# 8iPanel.net
KiCad netlist of a schematic drawn in EAGLE
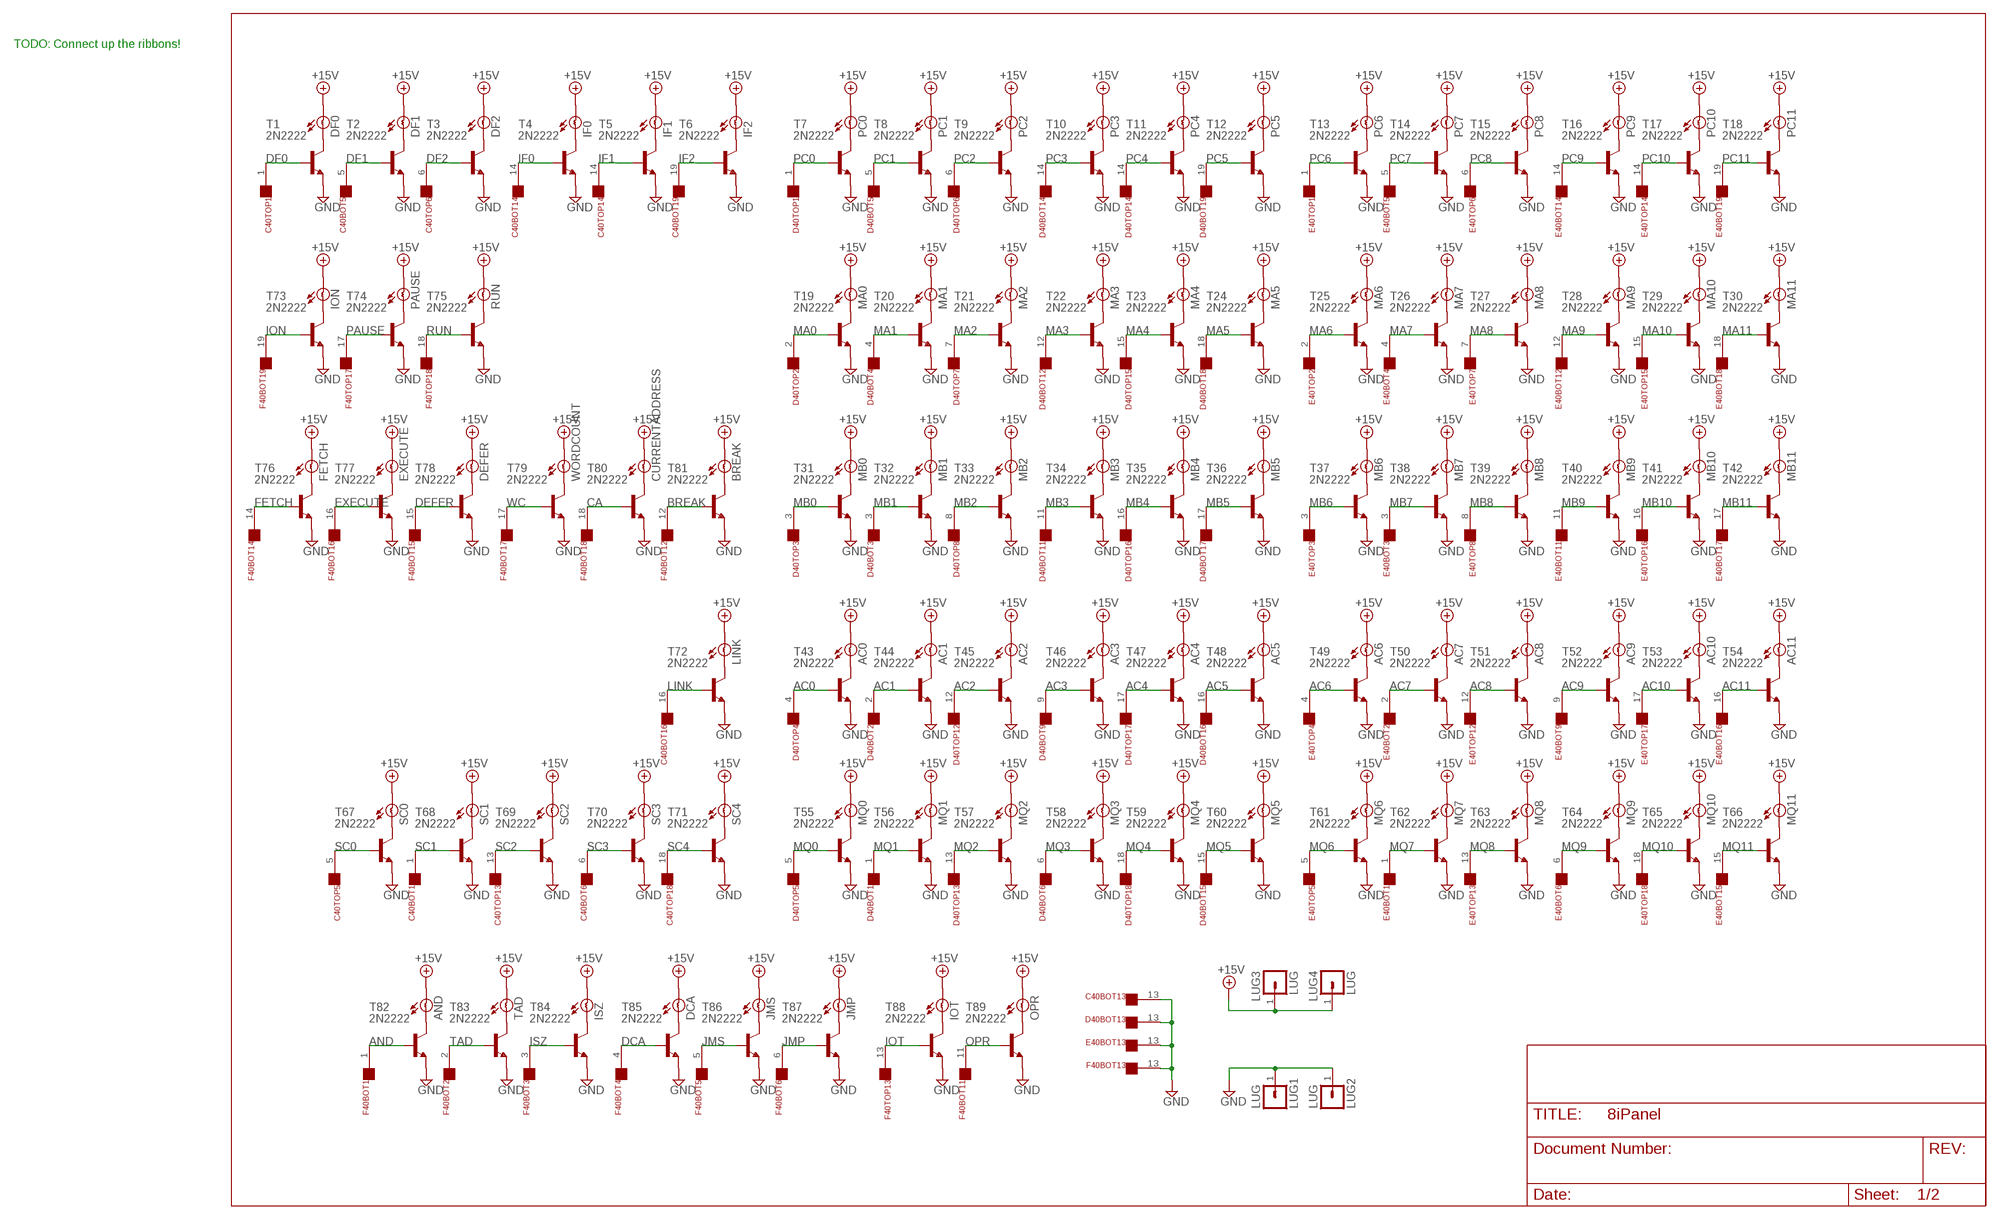
[diagram p0: schematic, sheet 1]
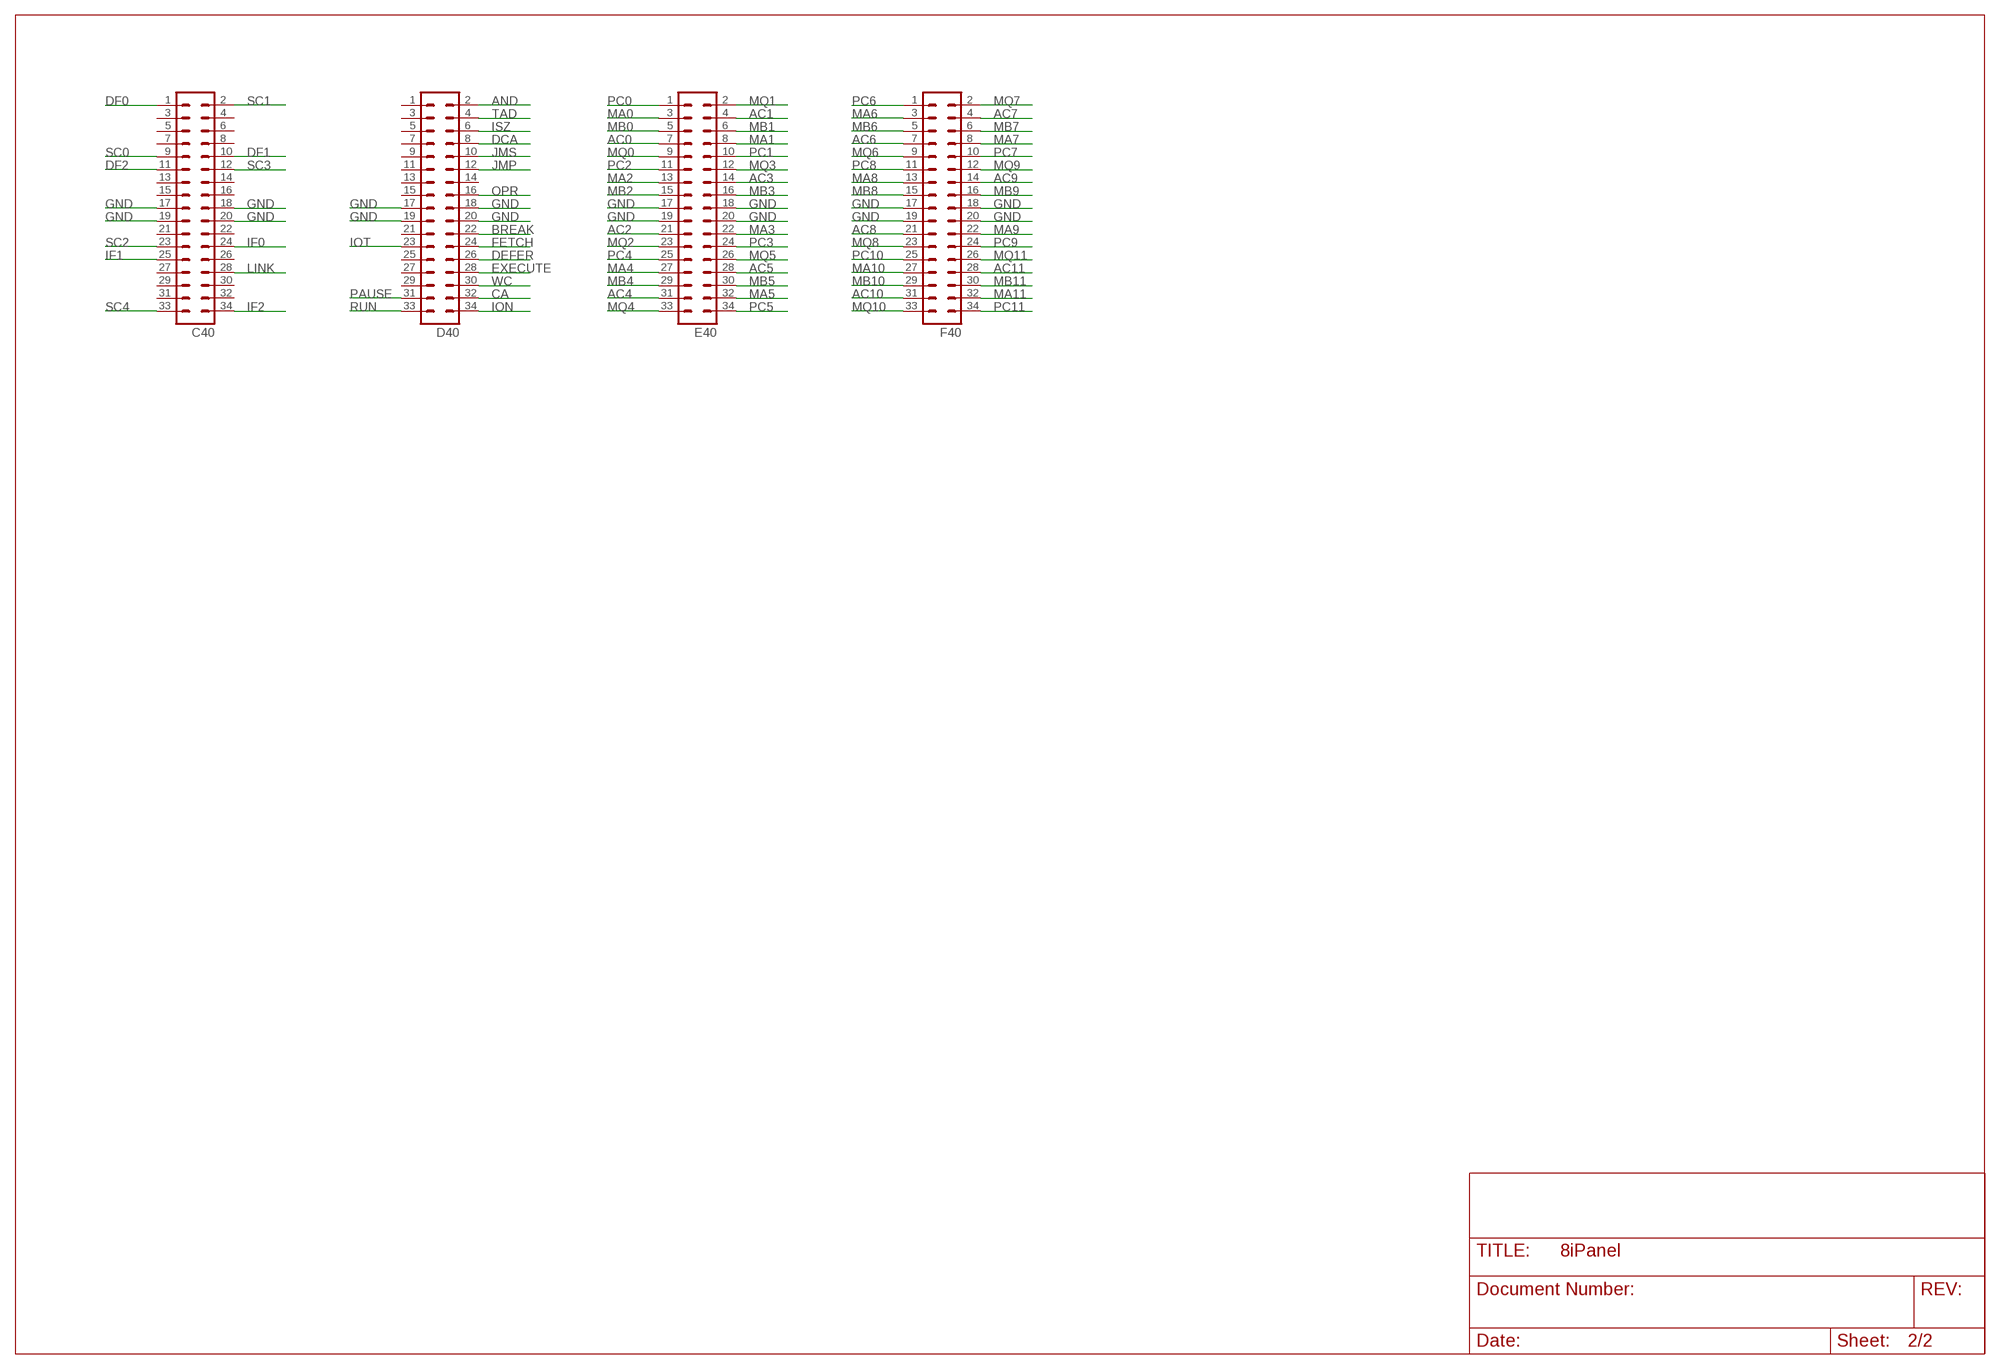
[diagram p1: schematic, sheet 2]

(export (version "E")
  (design (tool "Eeschema 10.0.6"))
  (components
    (comp (ref "AC0")
      (value "BULB")
      (footprint "eagle-import:BULB")
      (libsource (lib "eagle-import") (part "BULB"))
    )
    (comp (ref "AC1")
      (value "BULB")
      (footprint "eagle-import:BULB")
      (libsource (lib "eagle-import") (part "BULB"))
    )
    (comp (ref "AC2")
      (value "BULB")
      (footprint "eagle-import:BULB")
      (libsource (lib "eagle-import") (part "BULB"))
    )
    (comp (ref "AC3")
      (value "BULB")
      (footprint "eagle-import:BULB")
      (libsource (lib "eagle-import") (part "BULB"))
    )
    (comp (ref "AC4")
      (value "BULB")
      (footprint "eagle-import:BULB")
      (libsource (lib "eagle-import") (part "BULB"))
    )
    (comp (ref "AC5")
      (value "BULB")
      (footprint "eagle-import:BULB")
      (libsource (lib "eagle-import") (part "BULB"))
    )
    (comp (ref "AC6")
      (value "BULB")
      (footprint "eagle-import:BULB")
      (libsource (lib "eagle-import") (part "BULB"))
    )
    (comp (ref "AC7")
      (value "BULB")
      (footprint "eagle-import:BULB")
      (libsource (lib "eagle-import") (part "BULB"))
    )
    (comp (ref "AC8")
      (value "BULB")
      (footprint "eagle-import:BULB")
      (libsource (lib "eagle-import") (part "BULB"))
    )
    (comp (ref "AC9")
      (value "BULB")
      (footprint "eagle-import:BULB")
      (libsource (lib "eagle-import") (part "BULB"))
    )
    (comp (ref "AC10")
      (value "BULB")
      (footprint "eagle-import:BULB")
      (libsource (lib "eagle-import") (part "BULB"))
    )
    (comp (ref "AC11")
      (value "BULB")
      (footprint "eagle-import:BULB")
      (libsource (lib "eagle-import") (part "BULB"))
    )
    (comp (ref "AND")
      (value "BULB")
      (footprint "eagle-import:BULB")
      (libsource (lib "eagle-import") (part "BULB"))
    )
    (comp (ref "BREAK")
      (value "BULB")
      (footprint "eagle-import:BULB")
      (libsource (lib "eagle-import") (part "BULB"))
    )
    (comp (ref "C40BOT")
      (value "FLEX19")
      (footprint "eagle-import:FLEX19")
      (libsource (lib "eagle-import") (part "FLEX19"))
    )
    (comp (ref "C40TOP")
      (value "FLEX19")
      (footprint "eagle-import:FLEX19")
      (libsource (lib "eagle-import") (part "FLEX19"))
    )
    (comp (ref "CURRENTADDRESS")
      (value "BULB")
      (footprint "eagle-import:BULB")
      (libsource (lib "eagle-import") (part "BULB"))
    )
    (comp (ref "D40BOT")
      (value "FLEX19")
      (footprint "eagle-import:FLEX19")
      (libsource (lib "eagle-import") (part "FLEX19"))
    )
    (comp (ref "D40TOP")
      (value "FLEX19")
      (footprint "eagle-import:FLEX19")
      (libsource (lib "eagle-import") (part "FLEX19"))
    )
    (comp (ref "DCA")
      (value "BULB")
      (footprint "eagle-import:BULB")
      (libsource (lib "eagle-import") (part "BULB"))
    )
    (comp (ref "DEFER")
      (value "BULB")
      (footprint "eagle-import:BULB")
      (libsource (lib "eagle-import") (part "BULB"))
    )
    (comp (ref "DF0")
      (value "BULB")
      (footprint "eagle-import:BULB")
      (libsource (lib "eagle-import") (part "BULB"))
    )
    (comp (ref "DF1")
      (value "BULB")
      (footprint "eagle-import:BULB")
      (libsource (lib "eagle-import") (part "BULB"))
    )
    (comp (ref "DF2")
      (value "BULB")
      (footprint "eagle-import:BULB")
      (libsource (lib "eagle-import") (part "BULB"))
    )
    (comp (ref "E40BOT")
      (value "FLEX19")
      (footprint "eagle-import:FLEX19")
      (libsource (lib "eagle-import") (part "FLEX19"))
    )
    (comp (ref "E40TOP")
      (value "FLEX19")
      (footprint "eagle-import:FLEX19")
      (libsource (lib "eagle-import") (part "FLEX19"))
    )
    (comp (ref "EXECUTE")
      (value "BULB")
      (footprint "eagle-import:BULB")
      (libsource (lib "eagle-import") (part "BULB"))
    )
    (comp (ref "F40BOT")
      (value "FLEX19")
      (footprint "eagle-import:FLEX19")
      (libsource (lib "eagle-import") (part "FLEX19"))
    )
    (comp (ref "F40TOP")
      (value "FLEX19")
      (footprint "eagle-import:FLEX19")
      (libsource (lib "eagle-import") (part "FLEX19"))
    )
    (comp (ref "FETCH")
      (value "BULB")
      (footprint "eagle-import:BULB")
      (libsource (lib "eagle-import") (part "BULB"))
    )
    (comp (ref "IF0")
      (value "BULB")
      (footprint "eagle-import:BULB")
      (libsource (lib "eagle-import") (part "BULB"))
    )
    (comp (ref "IF1")
      (value "BULB")
      (footprint "eagle-import:BULB")
      (libsource (lib "eagle-import") (part "BULB"))
    )
    (comp (ref "IF2")
      (value "BULB")
      (footprint "eagle-import:BULB")
      (libsource (lib "eagle-import") (part "BULB"))
    )
    (comp (ref "ION")
      (value "BULB")
      (footprint "eagle-import:BULB")
      (libsource (lib "eagle-import") (part "BULB"))
    )
    (comp (ref "IOT")
      (value "BULB")
      (footprint "eagle-import:BULB")
      (libsource (lib "eagle-import") (part "BULB"))
    )
    (comp (ref "ISZ")
      (value "BULB")
      (footprint "eagle-import:BULB")
      (libsource (lib "eagle-import") (part "BULB"))
    )
    (comp (ref "JMP")
      (value "BULB")
      (footprint "eagle-import:BULB")
      (libsource (lib "eagle-import") (part "BULB"))
    )
    (comp (ref "JMS")
      (value "BULB")
      (footprint "eagle-import:BULB")
      (libsource (lib "eagle-import") (part "BULB"))
    )
    (comp (ref "LINK")
      (value "BULB")
      (footprint "eagle-import:BULB")
      (libsource (lib "eagle-import") (part "BULB"))
    )
    (comp (ref "LUG1")
      (value "LUG")
      (footprint "eagle-import:SPADELUG")
      (libsource (lib "eagle-import") (part "LUG"))
    )
    (comp (ref "LUG2")
      (value "LUG")
      (footprint "eagle-import:SPADELUG")
      (libsource (lib "eagle-import") (part "LUG"))
    )
    (comp (ref "LUG3")
      (value "LUG")
      (footprint "eagle-import:SPADELUG")
      (libsource (lib "eagle-import") (part "LUG"))
    )
    (comp (ref "LUG4")
      (value "LUG")
      (footprint "eagle-import:SPADELUG")
      (libsource (lib "eagle-import") (part "LUG"))
    )
    (comp (ref "MA0")
      (value "BULB")
      (footprint "eagle-import:BULB")
      (libsource (lib "eagle-import") (part "BULB"))
    )
    (comp (ref "MA1")
      (value "BULB")
      (footprint "eagle-import:BULB")
      (libsource (lib "eagle-import") (part "BULB"))
    )
    (comp (ref "MA2")
      (value "BULB")
      (footprint "eagle-import:BULB")
      (libsource (lib "eagle-import") (part "BULB"))
    )
    (comp (ref "MA3")
      (value "BULB")
      (footprint "eagle-import:BULB")
      (libsource (lib "eagle-import") (part "BULB"))
    )
    (comp (ref "MA4")
      (value "BULB")
      (footprint "eagle-import:BULB")
      (libsource (lib "eagle-import") (part "BULB"))
    )
    (comp (ref "MA5")
      (value "BULB")
      (footprint "eagle-import:BULB")
      (libsource (lib "eagle-import") (part "BULB"))
    )
    (comp (ref "MA6")
      (value "BULB")
      (footprint "eagle-import:BULB")
      (libsource (lib "eagle-import") (part "BULB"))
    )
    (comp (ref "MA7")
      (value "BULB")
      (footprint "eagle-import:BULB")
      (libsource (lib "eagle-import") (part "BULB"))
    )
    (comp (ref "MA8")
      (value "BULB")
      (footprint "eagle-import:BULB")
      (libsource (lib "eagle-import") (part "BULB"))
    )
    (comp (ref "MA9")
      (value "BULB")
      (footprint "eagle-import:BULB")
      (libsource (lib "eagle-import") (part "BULB"))
    )
    (comp (ref "MA10")
      (value "BULB")
      (footprint "eagle-import:BULB")
      (libsource (lib "eagle-import") (part "BULB"))
    )
    (comp (ref "MA11")
      (value "BULB")
      (footprint "eagle-import:BULB")
      (libsource (lib "eagle-import") (part "BULB"))
    )
    (comp (ref "MB0")
      (value "BULB")
      (footprint "eagle-import:BULB")
      (libsource (lib "eagle-import") (part "BULB"))
    )
    (comp (ref "MB1")
      (value "BULB")
      (footprint "eagle-import:BULB")
      (libsource (lib "eagle-import") (part "BULB"))
    )
    (comp (ref "MB2")
      (value "BULB")
      (footprint "eagle-import:BULB")
      (libsource (lib "eagle-import") (part "BULB"))
    )
    (comp (ref "MB3")
      (value "BULB")
      (footprint "eagle-import:BULB")
      (libsource (lib "eagle-import") (part "BULB"))
    )
    (comp (ref "MB4")
      (value "BULB")
      (footprint "eagle-import:BULB")
      (libsource (lib "eagle-import") (part "BULB"))
    )
    (comp (ref "MB5")
      (value "BULB")
      (footprint "eagle-import:BULB")
      (libsource (lib "eagle-import") (part "BULB"))
    )
    (comp (ref "MB6")
      (value "BULB")
      (footprint "eagle-import:BULB")
      (libsource (lib "eagle-import") (part "BULB"))
    )
    (comp (ref "MB7")
      (value "BULB")
      (footprint "eagle-import:BULB")
      (libsource (lib "eagle-import") (part "BULB"))
    )
    (comp (ref "MB8")
      (value "BULB")
      (footprint "eagle-import:BULB")
      (libsource (lib "eagle-import") (part "BULB"))
    )
    (comp (ref "MB9")
      (value "BULB")
      (footprint "eagle-import:BULB")
      (libsource (lib "eagle-import") (part "BULB"))
    )
    (comp (ref "MB10")
      (value "BULB")
      (footprint "eagle-import:BULB")
      (libsource (lib "eagle-import") (part "BULB"))
    )
    (comp (ref "MB11")
      (value "BULB")
      (footprint "eagle-import:BULB")
      (libsource (lib "eagle-import") (part "BULB"))
    )
    (comp (ref "MQ0")
      (value "BULB")
      (footprint "eagle-import:BULB")
      (libsource (lib "eagle-import") (part "BULB"))
    )
    (comp (ref "MQ1")
      (value "BULB")
      (footprint "eagle-import:BULB")
      (libsource (lib "eagle-import") (part "BULB"))
    )
    (comp (ref "MQ2")
      (value "BULB")
      (footprint "eagle-import:BULB")
      (libsource (lib "eagle-import") (part "BULB"))
    )
    (comp (ref "MQ3")
      (value "BULB")
      (footprint "eagle-import:BULB")
      (libsource (lib "eagle-import") (part "BULB"))
    )
    (comp (ref "MQ4")
      (value "BULB")
      (footprint "eagle-import:BULB")
      (libsource (lib "eagle-import") (part "BULB"))
    )
    (comp (ref "MQ5")
      (value "BULB")
      (footprint "eagle-import:BULB")
      (libsource (lib "eagle-import") (part "BULB"))
    )
    (comp (ref "MQ6")
      (value "BULB")
      (footprint "eagle-import:BULB")
      (libsource (lib "eagle-import") (part "BULB"))
    )
    (comp (ref "MQ7")
      (value "BULB")
      (footprint "eagle-import:BULB")
      (libsource (lib "eagle-import") (part "BULB"))
    )
    (comp (ref "MQ8")
      (value "BULB")
      (footprint "eagle-import:BULB")
      (libsource (lib "eagle-import") (part "BULB"))
    )
    (comp (ref "MQ9")
      (value "BULB")
      (footprint "eagle-import:BULB")
      (libsource (lib "eagle-import") (part "BULB"))
    )
    (comp (ref "MQ10")
      (value "BULB")
      (footprint "eagle-import:BULB")
      (libsource (lib "eagle-import") (part "BULB"))
    )
    (comp (ref "MQ11")
      (value "BULB")
      (footprint "eagle-import:BULB")
      (libsource (lib "eagle-import") (part "BULB"))
    )
    (comp (ref "OPR")
      (value "BULB")
      (footprint "eagle-import:BULB")
      (libsource (lib "eagle-import") (part "BULB"))
    )
    (comp (ref "PAUSE")
      (value "BULB")
      (footprint "eagle-import:BULB")
      (libsource (lib "eagle-import") (part "BULB"))
    )
    (comp (ref "PC0")
      (value "BULB")
      (footprint "eagle-import:BULB")
      (libsource (lib "eagle-import") (part "BULB"))
    )
    (comp (ref "PC1")
      (value "BULB")
      (footprint "eagle-import:BULB")
      (libsource (lib "eagle-import") (part "BULB"))
    )
    (comp (ref "PC2")
      (value "BULB")
      (footprint "eagle-import:BULB")
      (libsource (lib "eagle-import") (part "BULB"))
    )
    (comp (ref "PC3")
      (value "BULB")
      (footprint "eagle-import:BULB")
      (libsource (lib "eagle-import") (part "BULB"))
    )
    (comp (ref "PC4")
      (value "BULB")
      (footprint "eagle-import:BULB")
      (libsource (lib "eagle-import") (part "BULB"))
    )
    (comp (ref "PC5")
      (value "BULB")
      (footprint "eagle-import:BULB")
      (libsource (lib "eagle-import") (part "BULB"))
    )
    (comp (ref "PC6")
      (value "BULB")
      (footprint "eagle-import:BULB")
      (libsource (lib "eagle-import") (part "BULB"))
    )
    (comp (ref "PC7")
      (value "BULB")
      (footprint "eagle-import:BULB")
      (libsource (lib "eagle-import") (part "BULB"))
    )
    (comp (ref "PC8")
      (value "BULB")
      (footprint "eagle-import:BULB")
      (libsource (lib "eagle-import") (part "BULB"))
    )
    (comp (ref "PC9")
      (value "BULB")
      (footprint "eagle-import:BULB")
      (libsource (lib "eagle-import") (part "BULB"))
    )
    (comp (ref "PC10")
      (value "BULB")
      (footprint "eagle-import:BULB")
      (libsource (lib "eagle-import") (part "BULB"))
    )
    (comp (ref "PC11")
      (value "BULB")
      (footprint "eagle-import:BULB")
      (libsource (lib "eagle-import") (part "BULB"))
    )
    (comp (ref "RUN")
      (value "BULB")
      (footprint "eagle-import:BULB")
      (libsource (lib "eagle-import") (part "BULB"))
    )
    (comp (ref "SC0")
      (value "BULB")
      (footprint "eagle-import:BULB")
      (libsource (lib "eagle-import") (part "BULB"))
    )
    (comp (ref "SC1")
      (value "BULB")
      (footprint "eagle-import:BULB")
      (libsource (lib "eagle-import") (part "BULB"))
    )
    (comp (ref "SC2")
      (value "BULB")
      (footprint "eagle-import:BULB")
      (libsource (lib "eagle-import") (part "BULB"))
    )
    (comp (ref "SC3")
      (value "BULB")
      (footprint "eagle-import:BULB")
      (libsource (lib "eagle-import") (part "BULB"))
    )
    (comp (ref "SC4")
      (value "BULB")
      (footprint "eagle-import:BULB")
      (libsource (lib "eagle-import") (part "BULB"))
    )
    (comp (ref "T1")
      (value "2N2222")
      (footprint "eagle-import:TO92")
      (libsource (lib "eagle-import") (part "-NPN-TO92"))
    )
    (comp (ref "T2")
      (value "2N2222")
      (footprint "eagle-import:TO92")
      (libsource (lib "eagle-import") (part "-NPN-TO92"))
    )
    (comp (ref "T3")
      (value "2N2222")
      (footprint "eagle-import:TO92")
      (libsource (lib "eagle-import") (part "-NPN-TO92"))
    )
    (comp (ref "T4")
      (value "2N2222")
      (footprint "eagle-import:TO92")
      (libsource (lib "eagle-import") (part "-NPN-TO92"))
    )
    (comp (ref "T5")
      (value "2N2222")
      (footprint "eagle-import:TO92")
      (libsource (lib "eagle-import") (part "-NPN-TO92"))
    )
    (comp (ref "T6")
      (value "2N2222")
      (footprint "eagle-import:TO92")
      (libsource (lib "eagle-import") (part "-NPN-TO92"))
    )
    (comp (ref "T7")
      (value "2N2222")
      (footprint "eagle-import:TO92")
      (libsource (lib "eagle-import") (part "-NPN-TO92"))
    )
    (comp (ref "T8")
      (value "2N2222")
      (footprint "eagle-import:TO92")
      (libsource (lib "eagle-import") (part "-NPN-TO92"))
    )
    (comp (ref "T9")
      (value "2N2222")
      (footprint "eagle-import:TO92")
      (libsource (lib "eagle-import") (part "-NPN-TO92"))
    )
    (comp (ref "T10")
      (value "2N2222")
      (footprint "eagle-import:TO92")
      (libsource (lib "eagle-import") (part "-NPN-TO92"))
    )
    (comp (ref "T11")
      (value "2N2222")
      (footprint "eagle-import:TO92")
      (libsource (lib "eagle-import") (part "-NPN-TO92"))
    )
    (comp (ref "T12")
      (value "2N2222")
      (footprint "eagle-import:TO92")
      (libsource (lib "eagle-import") (part "-NPN-TO92"))
    )
    (comp (ref "T13")
      (value "2N2222")
      (footprint "eagle-import:TO92")
      (libsource (lib "eagle-import") (part "-NPN-TO92"))
    )
    (comp (ref "T14")
      (value "2N2222")
      (footprint "eagle-import:TO92")
      (libsource (lib "eagle-import") (part "-NPN-TO92"))
    )
    (comp (ref "T15")
      (value "2N2222")
      (footprint "eagle-import:TO92")
      (libsource (lib "eagle-import") (part "-NPN-TO92"))
    )
    (comp (ref "T16")
      (value "2N2222")
      (footprint "eagle-import:TO92")
      (libsource (lib "eagle-import") (part "-NPN-TO92"))
    )
    (comp (ref "T17")
      (value "2N2222")
      (footprint "eagle-import:TO92")
      (libsource (lib "eagle-import") (part "-NPN-TO92"))
    )
    (comp (ref "T18")
      (value "2N2222")
      (footprint "eagle-import:TO92")
      (libsource (lib "eagle-import") (part "-NPN-TO92"))
    )
    (comp (ref "T19")
      (value "2N2222")
      (footprint "eagle-import:TO92")
      (libsource (lib "eagle-import") (part "-NPN-TO92"))
    )
    (comp (ref "T20")
      (value "2N2222")
      (footprint "eagle-import:TO92")
      (libsource (lib "eagle-import") (part "-NPN-TO92"))
    )
    (comp (ref "T21")
      (value "2N2222")
      (footprint "eagle-import:TO92")
      (libsource (lib "eagle-import") (part "-NPN-TO92"))
    )
    (comp (ref "T22")
      (value "2N2222")
      (footprint "eagle-import:TO92")
      (libsource (lib "eagle-import") (part "-NPN-TO92"))
    )
    (comp (ref "T23")
      (value "2N2222")
      (footprint "eagle-import:TO92")
      (libsource (lib "eagle-import") (part "-NPN-TO92"))
    )
    (comp (ref "T24")
      (value "2N2222")
      (footprint "eagle-import:TO92")
      (libsource (lib "eagle-import") (part "-NPN-TO92"))
    )
    (comp (ref "T25")
      (value "2N2222")
      (footprint "eagle-import:TO92")
      (libsource (lib "eagle-import") (part "-NPN-TO92"))
    )
    (comp (ref "T26")
      (value "2N2222")
      (footprint "eagle-import:TO92")
      (libsource (lib "eagle-import") (part "-NPN-TO92"))
    )
    (comp (ref "T27")
      (value "2N2222")
      (footprint "eagle-import:TO92")
      (libsource (lib "eagle-import") (part "-NPN-TO92"))
    )
    (comp (ref "T28")
      (value "2N2222")
      (footprint "eagle-import:TO92")
      (libsource (lib "eagle-import") (part "-NPN-TO92"))
    )
    (comp (ref "T29")
      (value "2N2222")
      (footprint "eagle-import:TO92")
      (libsource (lib "eagle-import") (part "-NPN-TO92"))
    )
    (comp (ref "T30")
      (value "2N2222")
      (footprint "eagle-import:TO92")
      (libsource (lib "eagle-import") (part "-NPN-TO92"))
    )
    (comp (ref "T31")
      (value "2N2222")
      (footprint "eagle-import:TO92")
      (libsource (lib "eagle-import") (part "-NPN-TO92"))
    )
    (comp (ref "T32")
      (value "2N2222")
      (footprint "eagle-import:TO92")
      (libsource (lib "eagle-import") (part "-NPN-TO92"))
    )
    (comp (ref "T33")
      (value "2N2222")
      (footprint "eagle-import:TO92")
      (libsource (lib "eagle-import") (part "-NPN-TO92"))
    )
    (comp (ref "T34")
      (value "2N2222")
      (footprint "eagle-import:TO92")
      (libsource (lib "eagle-import") (part "-NPN-TO92"))
    )
    (comp (ref "T35")
      (value "2N2222")
      (footprint "eagle-import:TO92")
      (libsource (lib "eagle-import") (part "-NPN-TO92"))
    )
    (comp (ref "T36")
      (value "2N2222")
      (footprint "eagle-import:TO92")
      (libsource (lib "eagle-import") (part "-NPN-TO92"))
    )
    (comp (ref "T37")
      (value "2N2222")
      (footprint "eagle-import:TO92")
      (libsource (lib "eagle-import") (part "-NPN-TO92"))
    )
    (comp (ref "T38")
      (value "2N2222")
      (footprint "eagle-import:TO92")
      (libsource (lib "eagle-import") (part "-NPN-TO92"))
    )
    (comp (ref "T39")
      (value "2N2222")
      (footprint "eagle-import:TO92")
      (libsource (lib "eagle-import") (part "-NPN-TO92"))
    )
    (comp (ref "T40")
      (value "2N2222")
      (footprint "eagle-import:TO92")
      (libsource (lib "eagle-import") (part "-NPN-TO92"))
    )
    (comp (ref "T41")
      (value "2N2222")
      (footprint "eagle-import:TO92")
      (libsource (lib "eagle-import") (part "-NPN-TO92"))
    )
    (comp (ref "T42")
      (value "2N2222")
      (footprint "eagle-import:TO92")
      (libsource (lib "eagle-import") (part "-NPN-TO92"))
    )
    (comp (ref "T43")
      (value "2N2222")
      (footprint "eagle-import:TO92")
      (libsource (lib "eagle-import") (part "-NPN-TO92"))
    )
    (comp (ref "T44")
      (value "2N2222")
      (footprint "eagle-import:TO92")
      (libsource (lib "eagle-import") (part "-NPN-TO92"))
    )
    (comp (ref "T45")
      (value "2N2222")
      (footprint "eagle-import:TO92")
      (libsource (lib "eagle-import") (part "-NPN-TO92"))
    )
    (comp (ref "T46")
      (value "2N2222")
      (footprint "eagle-import:TO92")
      (libsource (lib "eagle-import") (part "-NPN-TO92"))
    )
    (comp (ref "T47")
      (value "2N2222")
      (footprint "eagle-import:TO92")
      (libsource (lib "eagle-import") (part "-NPN-TO92"))
    )
    (comp (ref "T48")
      (value "2N2222")
      (footprint "eagle-import:TO92")
      (libsource (lib "eagle-import") (part "-NPN-TO92"))
    )
    (comp (ref "T49")
      (value "2N2222")
      (footprint "eagle-import:TO92")
      (libsource (lib "eagle-import") (part "-NPN-TO92"))
    )
    (comp (ref "T50")
      (value "2N2222")
      (footprint "eagle-import:TO92")
      (libsource (lib "eagle-import") (part "-NPN-TO92"))
    )
    (comp (ref "T51")
      (value "2N2222")
      (footprint "eagle-import:TO92")
      (libsource (lib "eagle-import") (part "-NPN-TO92"))
    )
    (comp (ref "T52")
      (value "2N2222")
      (footprint "eagle-import:TO92")
      (libsource (lib "eagle-import") (part "-NPN-TO92"))
    )
    (comp (ref "T53")
      (value "2N2222")
      (footprint "eagle-import:TO92")
      (libsource (lib "eagle-import") (part "-NPN-TO92"))
    )
    (comp (ref "T54")
      (value "2N2222")
      (footprint "eagle-import:TO92")
      (libsource (lib "eagle-import") (part "-NPN-TO92"))
    )
    (comp (ref "T55")
      (value "2N2222")
      (footprint "eagle-import:TO92")
      (libsource (lib "eagle-import") (part "-NPN-TO92"))
    )
    (comp (ref "T56")
      (value "2N2222")
      (footprint "eagle-import:TO92")
      (libsource (lib "eagle-import") (part "-NPN-TO92"))
    )
    (comp (ref "T57")
      (value "2N2222")
      (footprint "eagle-import:TO92")
      (libsource (lib "eagle-import") (part "-NPN-TO92"))
    )
    (comp (ref "T58")
      (value "2N2222")
      (footprint "eagle-import:TO92")
      (libsource (lib "eagle-import") (part "-NPN-TO92"))
    )
    (comp (ref "T59")
      (value "2N2222")
      (footprint "eagle-import:TO92")
      (libsource (lib "eagle-import") (part "-NPN-TO92"))
    )
    (comp (ref "T60")
      (value "2N2222")
      (footprint "eagle-import:TO92")
      (libsource (lib "eagle-import") (part "-NPN-TO92"))
    )
    (comp (ref "T61")
      (value "2N2222")
      (footprint "eagle-import:TO92")
      (libsource (lib "eagle-import") (part "-NPN-TO92"))
    )
    (comp (ref "T62")
      (value "2N2222")
      (footprint "eagle-import:TO92")
      (libsource (lib "eagle-import") (part "-NPN-TO92"))
    )
    (comp (ref "T63")
      (value "2N2222")
      (footprint "eagle-import:TO92")
      (libsource (lib "eagle-import") (part "-NPN-TO92"))
    )
    (comp (ref "T64")
      (value "2N2222")
      (footprint "eagle-import:TO92")
      (libsource (lib "eagle-import") (part "-NPN-TO92"))
    )
    (comp (ref "T65")
      (value "2N2222")
      (footprint "eagle-import:TO92")
      (libsource (lib "eagle-import") (part "-NPN-TO92"))
    )
    (comp (ref "T66")
      (value "2N2222")
      (footprint "eagle-import:TO92")
      (libsource (lib "eagle-import") (part "-NPN-TO92"))
    )
    (comp (ref "T67")
      (value "2N2222")
      (footprint "eagle-import:TO92")
      (libsource (lib "eagle-import") (part "-NPN-TO92"))
    )
    (comp (ref "T68")
      (value "2N2222")
      (footprint "eagle-import:TO92")
      (libsource (lib "eagle-import") (part "-NPN-TO92"))
    )
    (comp (ref "T69")
      (value "2N2222")
      (footprint "eagle-import:TO92")
      (libsource (lib "eagle-import") (part "-NPN-TO92"))
    )
    (comp (ref "T70")
      (value "2N2222")
      (footprint "eagle-import:TO92")
      (libsource (lib "eagle-import") (part "-NPN-TO92"))
    )
    (comp (ref "T71")
      (value "2N2222")
      (footprint "eagle-import:TO92")
      (libsource (lib "eagle-import") (part "-NPN-TO92"))
    )
    (comp (ref "T72")
      (value "2N2222")
      (footprint "eagle-import:TO92")
      (libsource (lib "eagle-import") (part "-NPN-TO92"))
    )
    (comp (ref "T73")
      (value "2N2222")
      (footprint "eagle-import:TO92")
      (libsource (lib "eagle-import") (part "-NPN-TO92"))
    )
    (comp (ref "T74")
      (value "2N2222")
      (footprint "eagle-import:TO92")
      (libsource (lib "eagle-import") (part "-NPN-TO92"))
    )
    (comp (ref "T75")
      (value "2N2222")
      (footprint "eagle-import:TO92")
      (libsource (lib "eagle-import") (part "-NPN-TO92"))
    )
    (comp (ref "T76")
      (value "2N2222")
      (footprint "eagle-import:TO92")
      (libsource (lib "eagle-import") (part "-NPN-TO92"))
    )
    (comp (ref "T77")
      (value "2N2222")
      (footprint "eagle-import:TO92")
      (libsource (lib "eagle-import") (part "-NPN-TO92"))
    )
    (comp (ref "T78")
      (value "2N2222")
      (footprint "eagle-import:TO92")
      (libsource (lib "eagle-import") (part "-NPN-TO92"))
    )
    (comp (ref "T79")
      (value "2N2222")
      (footprint "eagle-import:TO92")
      (libsource (lib "eagle-import") (part "-NPN-TO92"))
    )
    (comp (ref "T80")
      (value "2N2222")
      (footprint "eagle-import:TO92")
      (libsource (lib "eagle-import") (part "-NPN-TO92"))
    )
    (comp (ref "T81")
      (value "2N2222")
      (footprint "eagle-import:TO92")
      (libsource (lib "eagle-import") (part "-NPN-TO92"))
    )
    (comp (ref "T82")
      (value "2N2222")
      (footprint "eagle-import:TO92")
      (libsource (lib "eagle-import") (part "-NPN-TO92"))
    )
    (comp (ref "T83")
      (value "2N2222")
      (footprint "eagle-import:TO92")
      (libsource (lib "eagle-import") (part "-NPN-TO92"))
    )
    (comp (ref "T84")
      (value "2N2222")
      (footprint "eagle-import:TO92")
      (libsource (lib "eagle-import") (part "-NPN-TO92"))
    )
    (comp (ref "T85")
      (value "2N2222")
      (footprint "eagle-import:TO92")
      (libsource (lib "eagle-import") (part "-NPN-TO92"))
    )
    (comp (ref "T86")
      (value "2N2222")
      (footprint "eagle-import:TO92")
      (libsource (lib "eagle-import") (part "-NPN-TO92"))
    )
    (comp (ref "T87")
      (value "2N2222")
      (footprint "eagle-import:TO92")
      (libsource (lib "eagle-import") (part "-NPN-TO92"))
    )
    (comp (ref "T88")
      (value "2N2222")
      (footprint "eagle-import:TO92")
      (libsource (lib "eagle-import") (part "-NPN-TO92"))
    )
    (comp (ref "T89")
      (value "2N2222")
      (footprint "eagle-import:TO92")
      (libsource (lib "eagle-import") (part "-NPN-TO92"))
    )
    (comp (ref "TAD")
      (value "BULB")
      (footprint "eagle-import:BULB")
      (libsource (lib "eagle-import") (part "BULB"))
    )
    (comp (ref "WORDCOUNT")
      (value "BULB")
      (footprint "eagle-import:BULB")
      (libsource (lib "eagle-import") (part "BULB"))
    )
    (comp (ref "C40")
      (value "MA17-2")
      (footprint "eagle-import:MA17-2")
      (libsource (lib "eagle-import") (part "MA17-2"))
    )
    (comp (ref "D40")
      (value "MA17-2")
      (footprint "eagle-import:MA17-2")
      (libsource (lib "eagle-import") (part "MA17-2"))
    )
    (comp (ref "E40")
      (value "MA17-2")
      (footprint "eagle-import:MA17-2")
      (libsource (lib "eagle-import") (part "MA17-2"))
    )
    (comp (ref "F40")
      (value "MA17-2")
      (footprint "eagle-import:MA17-2")
      (libsource (lib "eagle-import") (part "MA17-2"))
    )
  )
  (nets
    (net (code "1") (name "+15V") (class "Default")
      (node (ref "AC0") (pin "A") (pinfunction "A_A") (pintype "passive"))
      (node (ref "AC1") (pin "A") (pinfunction "A_A") (pintype "passive"))
      (node (ref "AC10") (pin "A") (pinfunction "A_A") (pintype "passive"))
      (node (ref "AC11") (pin "A") (pinfunction "A_A") (pintype "passive"))
      (node (ref "AC2") (pin "A") (pinfunction "A_A") (pintype "passive"))
      (node (ref "AC3") (pin "A") (pinfunction "A_A") (pintype "passive"))
      (node (ref "AC4") (pin "A") (pinfunction "A_A") (pintype "passive"))
      (node (ref "AC5") (pin "A") (pinfunction "A_A") (pintype "passive"))
      (node (ref "AC6") (pin "A") (pinfunction "A_A") (pintype "passive"))
      (node (ref "AC7") (pin "A") (pinfunction "A_A") (pintype "passive"))
      (node (ref "AC8") (pin "A") (pinfunction "A_A") (pintype "passive"))
      (node (ref "AC9") (pin "A") (pinfunction "A_A") (pintype "passive"))
      (node (ref "AND") (pin "A") (pinfunction "A_A") (pintype "passive"))
      (node (ref "BREAK") (pin "A") (pinfunction "A_A") (pintype "passive"))
      (node (ref "CURRENTADDRESS") (pin "A") (pinfunction "A_A") (pintype "passive"))
      (node (ref "DCA") (pin "A") (pinfunction "A_A") (pintype "passive"))
      (node (ref "DEFER") (pin "A") (pinfunction "A_A") (pintype "passive"))
      (node (ref "DF0") (pin "A") (pinfunction "A_A") (pintype "passive"))
      (node (ref "DF1") (pin "A") (pinfunction "A_A") (pintype "passive"))
      (node (ref "DF2") (pin "A") (pinfunction "A_A") (pintype "passive"))
      (node (ref "EXECUTE") (pin "A") (pinfunction "A_A") (pintype "passive"))
      (node (ref "FETCH") (pin "A") (pinfunction "A_A") (pintype "passive"))
      (node (ref "IF0") (pin "A") (pinfunction "A_A") (pintype "passive"))
      (node (ref "IF1") (pin "A") (pinfunction "A_A") (pintype "passive"))
      (node (ref "IF2") (pin "A") (pinfunction "A_A") (pintype "passive"))
      (node (ref "ION") (pin "A") (pinfunction "A_A") (pintype "passive"))
      (node (ref "IOT") (pin "A") (pinfunction "A_A") (pintype "passive"))
      (node (ref "ISZ") (pin "A") (pinfunction "A_A") (pintype "passive"))
      (node (ref "JMP") (pin "A") (pinfunction "A_A") (pintype "passive"))
      (node (ref "JMS") (pin "A") (pinfunction "A_A") (pintype "passive"))
      (node (ref "LINK") (pin "A") (pinfunction "A_A") (pintype "passive"))
      (node (ref "LUG3") (pin "1") (pinfunction "1_1") (pintype "passive"))
      (node (ref "LUG4") (pin "1") (pinfunction "1_1") (pintype "passive"))
      (node (ref "MA0") (pin "A") (pinfunction "A_A") (pintype "passive"))
      (node (ref "MA1") (pin "A") (pinfunction "A_A") (pintype "passive"))
      (node (ref "MA10") (pin "A") (pinfunction "A_A") (pintype "passive"))
      (node (ref "MA11") (pin "A") (pinfunction "A_A") (pintype "passive"))
      (node (ref "MA2") (pin "A") (pinfunction "A_A") (pintype "passive"))
      (node (ref "MA3") (pin "A") (pinfunction "A_A") (pintype "passive"))
      (node (ref "MA4") (pin "A") (pinfunction "A_A") (pintype "passive"))
      (node (ref "MA5") (pin "A") (pinfunction "A_A") (pintype "passive"))
      (node (ref "MA6") (pin "A") (pinfunction "A_A") (pintype "passive"))
      (node (ref "MA7") (pin "A") (pinfunction "A_A") (pintype "passive"))
      (node (ref "MA8") (pin "A") (pinfunction "A_A") (pintype "passive"))
      (node (ref "MA9") (pin "A") (pinfunction "A_A") (pintype "passive"))
      (node (ref "MB0") (pin "A") (pinfunction "A_A") (pintype "passive"))
      (node (ref "MB1") (pin "A") (pinfunction "A_A") (pintype "passive"))
      (node (ref "MB10") (pin "A") (pinfunction "A_A") (pintype "passive"))
      (node (ref "MB11") (pin "A") (pinfunction "A_A") (pintype "passive"))
      (node (ref "MB2") (pin "A") (pinfunction "A_A") (pintype "passive"))
      (node (ref "MB3") (pin "A") (pinfunction "A_A") (pintype "passive"))
      (node (ref "MB4") (pin "A") (pinfunction "A_A") (pintype "passive"))
      (node (ref "MB5") (pin "A") (pinfunction "A_A") (pintype "passive"))
      (node (ref "MB6") (pin "A") (pinfunction "A_A") (pintype "passive"))
      (node (ref "MB7") (pin "A") (pinfunction "A_A") (pintype "passive"))
      (node (ref "MB8") (pin "A") (pinfunction "A_A") (pintype "passive"))
      (node (ref "MB9") (pin "A") (pinfunction "A_A") (pintype "passive"))
      (node (ref "MQ0") (pin "A") (pinfunction "A_A") (pintype "passive"))
      (node (ref "MQ1") (pin "A") (pinfunction "A_A") (pintype "passive"))
      (node (ref "MQ10") (pin "A") (pinfunction "A_A") (pintype "passive"))
      (node (ref "MQ11") (pin "A") (pinfunction "A_A") (pintype "passive"))
      (node (ref "MQ2") (pin "A") (pinfunction "A_A") (pintype "passive"))
      (node (ref "MQ3") (pin "A") (pinfunction "A_A") (pintype "passive"))
      (node (ref "MQ4") (pin "A") (pinfunction "A_A") (pintype "passive"))
      (node (ref "MQ5") (pin "A") (pinfunction "A_A") (pintype "passive"))
      (node (ref "MQ6") (pin "A") (pinfunction "A_A") (pintype "passive"))
      (node (ref "MQ7") (pin "A") (pinfunction "A_A") (pintype "passive"))
      (node (ref "MQ8") (pin "A") (pinfunction "A_A") (pintype "passive"))
      (node (ref "MQ9") (pin "A") (pinfunction "A_A") (pintype "passive"))
      (node (ref "OPR") (pin "A") (pinfunction "A_A") (pintype "passive"))
      (node (ref "PAUSE") (pin "A") (pinfunction "A_A") (pintype "passive"))
      (node (ref "PC0") (pin "A") (pinfunction "A_A") (pintype "passive"))
      (node (ref "PC1") (pin "A") (pinfunction "A_A") (pintype "passive"))
      (node (ref "PC10") (pin "A") (pinfunction "A_A") (pintype "passive"))
      (node (ref "PC11") (pin "A") (pinfunction "A_A") (pintype "passive"))
      (node (ref "PC2") (pin "A") (pinfunction "A_A") (pintype "passive"))
      (node (ref "PC3") (pin "A") (pinfunction "A_A") (pintype "passive"))
      (node (ref "PC4") (pin "A") (pinfunction "A_A") (pintype "passive"))
      (node (ref "PC5") (pin "A") (pinfunction "A_A") (pintype "passive"))
      (node (ref "PC6") (pin "A") (pinfunction "A_A") (pintype "passive"))
      (node (ref "PC7") (pin "A") (pinfunction "A_A") (pintype "passive"))
      (node (ref "PC8") (pin "A") (pinfunction "A_A") (pintype "passive"))
      (node (ref "PC9") (pin "A") (pinfunction "A_A") (pintype "passive"))
      (node (ref "RUN") (pin "A") (pinfunction "A_A") (pintype "passive"))
      (node (ref "SC0") (pin "A") (pinfunction "A_A") (pintype "passive"))
      (node (ref "SC1") (pin "A") (pinfunction "A_A") (pintype "passive"))
      (node (ref "SC2") (pin "A") (pinfunction "A_A") (pintype "passive"))
      (node (ref "SC3") (pin "A") (pinfunction "A_A") (pintype "passive"))
      (node (ref "SC4") (pin "A") (pinfunction "A_A") (pintype "passive"))
      (node (ref "TAD") (pin "A") (pinfunction "A_A") (pintype "passive"))
      (node (ref "WORDCOUNT") (pin "A") (pinfunction "A_A") (pintype "passive"))
    )
    (net (code "2") (name "AC0") (class "Default")
      (node (ref "D40TOP") (pin "4") (pinfunction "1_4") (pintype "passive"))
      (node (ref "E40") (pin "7") (pinfunction "7_7") (pintype "passive"))
      (node (ref "T43") (pin "2") (pinfunction "B_2") (pintype "passive"))
    )
    (net (code "3") (name "AC1") (class "Default")
      (node (ref "D40BOT") (pin "2") (pinfunction "1_2") (pintype "passive"))
      (node (ref "E40") (pin "4") (pinfunction "4_4") (pintype "passive"))
      (node (ref "T44") (pin "2") (pinfunction "B_2") (pintype "passive"))
    )
    (net (code "4") (name "AC2") (class "Default")
      (node (ref "D40TOP") (pin "12") (pinfunction "1_12") (pintype "passive"))
      (node (ref "E40") (pin "21") (pinfunction "21_21") (pintype "passive"))
      (node (ref "T45") (pin "2") (pinfunction "B_2") (pintype "passive"))
    )
    (net (code "5") (name "AC3") (class "Default")
      (node (ref "D40BOT") (pin "9") (pinfunction "1_9") (pintype "passive"))
      (node (ref "E40") (pin "14") (pinfunction "14_14") (pintype "passive"))
      (node (ref "T46") (pin "2") (pinfunction "B_2") (pintype "passive"))
    )
    (net (code "6") (name "AC4") (class "Default")
      (node (ref "D40TOP") (pin "17") (pinfunction "1_17") (pintype "passive"))
      (node (ref "E40") (pin "31") (pinfunction "31_31") (pintype "passive"))
      (node (ref "T47") (pin "2") (pinfunction "B_2") (pintype "passive"))
    )
    (net (code "7") (name "AC5") (class "Default")
      (node (ref "D40BOT") (pin "16") (pinfunction "1_16") (pintype "passive"))
      (node (ref "E40") (pin "28") (pinfunction "28_28") (pintype "passive"))
      (node (ref "T48") (pin "2") (pinfunction "B_2") (pintype "passive"))
    )
    (net (code "8") (name "AC6") (class "Default")
      (node (ref "E40TOP") (pin "4") (pinfunction "1_4") (pintype "passive"))
      (node (ref "F40") (pin "7") (pinfunction "7_7") (pintype "passive"))
      (node (ref "T49") (pin "2") (pinfunction "B_2") (pintype "passive"))
    )
    (net (code "9") (name "AC7") (class "Default")
      (node (ref "E40BOT") (pin "2") (pinfunction "1_2") (pintype "passive"))
      (node (ref "F40") (pin "4") (pinfunction "4_4") (pintype "passive"))
      (node (ref "T50") (pin "2") (pinfunction "B_2") (pintype "passive"))
    )
    (net (code "10") (name "AC8") (class "Default")
      (node (ref "E40TOP") (pin "12") (pinfunction "1_12") (pintype "passive"))
      (node (ref "F40") (pin "21") (pinfunction "21_21") (pintype "passive"))
      (node (ref "T51") (pin "2") (pinfunction "B_2") (pintype "passive"))
    )
    (net (code "11") (name "AC9") (class "Default")
      (node (ref "E40BOT") (pin "9") (pinfunction "1_9") (pintype "passive"))
      (node (ref "F40") (pin "14") (pinfunction "14_14") (pintype "passive"))
      (node (ref "T52") (pin "2") (pinfunction "B_2") (pintype "passive"))
    )
    (net (code "12") (name "AC10") (class "Default")
      (node (ref "E40TOP") (pin "17") (pinfunction "1_17") (pintype "passive"))
      (node (ref "F40") (pin "31") (pinfunction "31_31") (pintype "passive"))
      (node (ref "T53") (pin "2") (pinfunction "B_2") (pintype "passive"))
    )
    (net (code "13") (name "AC11") (class "Default")
      (node (ref "E40BOT") (pin "16") (pinfunction "1_16") (pintype "passive"))
      (node (ref "F40") (pin "28") (pinfunction "28_28") (pintype "passive"))
      (node (ref "T54") (pin "2") (pinfunction "B_2") (pintype "passive"))
    )
    (net (code "14") (name "AND") (class "Default")
      (node (ref "D40") (pin "2") (pinfunction "2_2") (pintype "passive"))
      (node (ref "F40BOT") (pin "1") (pinfunction "1_1") (pintype "passive"))
      (node (ref "T82") (pin "2") (pinfunction "B_2") (pintype "passive"))
    )
    (net (code "15") (name "BREAK") (class "Default")
      (node (ref "D40") (pin "22") (pinfunction "22_22") (pintype "passive"))
      (node (ref "F40BOT") (pin "12") (pinfunction "1_12") (pintype "passive"))
      (node (ref "T81") (pin "2") (pinfunction "B_2") (pintype "passive"))
    )
    (net (code "16") (name "CA") (class "Default")
      (node (ref "D40") (pin "32") (pinfunction "32_32") (pintype "passive"))
      (node (ref "F40BOT") (pin "18") (pinfunction "1_18") (pintype "passive"))
      (node (ref "T80") (pin "2") (pinfunction "B_2") (pintype "passive"))
    )
    (net (code "17") (name "DCA") (class "Default")
      (node (ref "D40") (pin "8") (pinfunction "8_8") (pintype "passive"))
      (node (ref "F40BOT") (pin "4") (pinfunction "1_4") (pintype "passive"))
      (node (ref "T85") (pin "2") (pinfunction "B_2") (pintype "passive"))
    )
    (net (code "18") (name "DEFER") (class "Default")
      (node (ref "D40") (pin "26") (pinfunction "26_26") (pintype "passive"))
      (node (ref "F40BOT") (pin "15") (pinfunction "1_15") (pintype "passive"))
      (node (ref "T78") (pin "2") (pinfunction "B_2") (pintype "passive"))
    )
    (net (code "19") (name "DF0") (class "Default")
      (node (ref "C40") (pin "1") (pinfunction "1_1") (pintype "passive"))
      (node (ref "C40TOP") (pin "1") (pinfunction "1_1") (pintype "passive"))
      (node (ref "T1") (pin "2") (pinfunction "B_2") (pintype "passive"))
    )
    (net (code "20") (name "DF1") (class "Default")
      (node (ref "C40") (pin "10") (pinfunction "10_10") (pintype "passive"))
      (node (ref "C40BOT") (pin "5") (pinfunction "1_5") (pintype "passive"))
      (node (ref "T2") (pin "2") (pinfunction "B_2") (pintype "passive"))
    )
    (net (code "21") (name "DF2") (class "Default")
      (node (ref "C40") (pin "11") (pinfunction "11_11") (pintype "passive"))
      (node (ref "C40TOP") (pin "6") (pinfunction "1_6") (pintype "passive"))
      (node (ref "T3") (pin "2") (pinfunction "B_2") (pintype "passive"))
    )
    (net (code "22") (name "EXECUTE") (class "Default")
      (node (ref "D40") (pin "28") (pinfunction "28_28") (pintype "passive"))
      (node (ref "F40BOT") (pin "16") (pinfunction "1_16") (pintype "passive"))
      (node (ref "T77") (pin "2") (pinfunction "B_2") (pintype "passive"))
    )
    (net (code "23") (name "FETCH") (class "Default")
      (node (ref "D40") (pin "24") (pinfunction "24_24") (pintype "passive"))
      (node (ref "F40BOT") (pin "14") (pinfunction "1_14") (pintype "passive"))
      (node (ref "T76") (pin "2") (pinfunction "B_2") (pintype "passive"))
    )
    (net (code "24") (name "GND") (class "Default")
      (node (ref "C40") (pin "17") (pinfunction "17_17") (pintype "passive"))
      (node (ref "C40") (pin "18") (pinfunction "18_18") (pintype "passive"))
      (node (ref "C40") (pin "19") (pinfunction "19_19") (pintype "passive"))
      (node (ref "C40") (pin "20") (pinfunction "20_20") (pintype "passive"))
      (node (ref "C40BOT") (pin "13") (pinfunction "1_13") (pintype "passive"))
      (node (ref "D40") (pin "17") (pinfunction "17_17") (pintype "passive"))
      (node (ref "D40") (pin "18") (pinfunction "18_18") (pintype "passive"))
      (node (ref "D40") (pin "19") (pinfunction "19_19") (pintype "passive"))
      (node (ref "D40") (pin "20") (pinfunction "20_20") (pintype "passive"))
      (node (ref "D40BOT") (pin "13") (pinfunction "1_13") (pintype "passive"))
      (node (ref "E40") (pin "17") (pinfunction "17_17") (pintype "passive"))
      (node (ref "E40") (pin "18") (pinfunction "18_18") (pintype "passive"))
      (node (ref "E40") (pin "19") (pinfunction "19_19") (pintype "passive"))
      (node (ref "E40") (pin "20") (pinfunction "20_20") (pintype "passive"))
      (node (ref "E40BOT") (pin "13") (pinfunction "1_13") (pintype "passive"))
      (node (ref "F40") (pin "17") (pinfunction "17_17") (pintype "passive"))
      (node (ref "F40") (pin "18") (pinfunction "18_18") (pintype "passive"))
      (node (ref "F40") (pin "19") (pinfunction "19_19") (pintype "passive"))
      (node (ref "F40") (pin "20") (pinfunction "20_20") (pintype "passive"))
      (node (ref "F40BOT") (pin "13") (pinfunction "1_13") (pintype "passive"))
      (node (ref "LUG1") (pin "1") (pinfunction "1_1") (pintype "passive"))
      (node (ref "LUG2") (pin "1") (pinfunction "1_1") (pintype "passive"))
      (node (ref "T1") (pin "1") (pinfunction "E_1") (pintype "passive"))
      (node (ref "T10") (pin "1") (pinfunction "E_1") (pintype "passive"))
      (node (ref "T11") (pin "1") (pinfunction "E_1") (pintype "passive"))
      (node (ref "T12") (pin "1") (pinfunction "E_1") (pintype "passive"))
      (node (ref "T13") (pin "1") (pinfunction "E_1") (pintype "passive"))
      (node (ref "T14") (pin "1") (pinfunction "E_1") (pintype "passive"))
      (node (ref "T15") (pin "1") (pinfunction "E_1") (pintype "passive"))
      (node (ref "T16") (pin "1") (pinfunction "E_1") (pintype "passive"))
      (node (ref "T17") (pin "1") (pinfunction "E_1") (pintype "passive"))
      (node (ref "T18") (pin "1") (pinfunction "E_1") (pintype "passive"))
      (node (ref "T19") (pin "1") (pinfunction "E_1") (pintype "passive"))
      (node (ref "T2") (pin "1") (pinfunction "E_1") (pintype "passive"))
      (node (ref "T20") (pin "1") (pinfunction "E_1") (pintype "passive"))
      (node (ref "T21") (pin "1") (pinfunction "E_1") (pintype "passive"))
      (node (ref "T22") (pin "1") (pinfunction "E_1") (pintype "passive"))
      (node (ref "T23") (pin "1") (pinfunction "E_1") (pintype "passive"))
      (node (ref "T24") (pin "1") (pinfunction "E_1") (pintype "passive"))
      (node (ref "T25") (pin "1") (pinfunction "E_1") (pintype "passive"))
      (node (ref "T26") (pin "1") (pinfunction "E_1") (pintype "passive"))
      (node (ref "T27") (pin "1") (pinfunction "E_1") (pintype "passive"))
      (node (ref "T28") (pin "1") (pinfunction "E_1") (pintype "passive"))
      (node (ref "T29") (pin "1") (pinfunction "E_1") (pintype "passive"))
      (node (ref "T3") (pin "1") (pinfunction "E_1") (pintype "passive"))
      (node (ref "T30") (pin "1") (pinfunction "E_1") (pintype "passive"))
      (node (ref "T31") (pin "1") (pinfunction "E_1") (pintype "passive"))
      (node (ref "T32") (pin "1") (pinfunction "E_1") (pintype "passive"))
      (node (ref "T33") (pin "1") (pinfunction "E_1") (pintype "passive"))
      (node (ref "T34") (pin "1") (pinfunction "E_1") (pintype "passive"))
      (node (ref "T35") (pin "1") (pinfunction "E_1") (pintype "passive"))
      (node (ref "T36") (pin "1") (pinfunction "E_1") (pintype "passive"))
      (node (ref "T37") (pin "1") (pinfunction "E_1") (pintype "passive"))
      (node (ref "T38") (pin "1") (pinfunction "E_1") (pintype "passive"))
      (node (ref "T39") (pin "1") (pinfunction "E_1") (pintype "passive"))
      (node (ref "T4") (pin "1") (pinfunction "E_1") (pintype "passive"))
      (node (ref "T40") (pin "1") (pinfunction "E_1") (pintype "passive"))
      (node (ref "T41") (pin "1") (pinfunction "E_1") (pintype "passive"))
      (node (ref "T42") (pin "1") (pinfunction "E_1") (pintype "passive"))
      (node (ref "T43") (pin "1") (pinfunction "E_1") (pintype "passive"))
      (node (ref "T44") (pin "1") (pinfunction "E_1") (pintype "passive"))
      (node (ref "T45") (pin "1") (pinfunction "E_1") (pintype "passive"))
      (node (ref "T46") (pin "1") (pinfunction "E_1") (pintype "passive"))
      (node (ref "T47") (pin "1") (pinfunction "E_1") (pintype "passive"))
      (node (ref "T48") (pin "1") (pinfunction "E_1") (pintype "passive"))
      (node (ref "T49") (pin "1") (pinfunction "E_1") (pintype "passive"))
      (node (ref "T5") (pin "1") (pinfunction "E_1") (pintype "passive"))
      (node (ref "T50") (pin "1") (pinfunction "E_1") (pintype "passive"))
      (node (ref "T51") (pin "1") (pinfunction "E_1") (pintype "passive"))
      (node (ref "T52") (pin "1") (pinfunction "E_1") (pintype "passive"))
      (node (ref "T53") (pin "1") (pinfunction "E_1") (pintype "passive"))
      (node (ref "T54") (pin "1") (pinfunction "E_1") (pintype "passive"))
      (node (ref "T55") (pin "1") (pinfunction "E_1") (pintype "passive"))
      (node (ref "T56") (pin "1") (pinfunction "E_1") (pintype "passive"))
      (node (ref "T57") (pin "1") (pinfunction "E_1") (pintype "passive"))
      (node (ref "T58") (pin "1") (pinfunction "E_1") (pintype "passive"))
      (node (ref "T59") (pin "1") (pinfunction "E_1") (pintype "passive"))
      (node (ref "T6") (pin "1") (pinfunction "E_1") (pintype "passive"))
      (node (ref "T60") (pin "1") (pinfunction "E_1") (pintype "passive"))
      (node (ref "T61") (pin "1") (pinfunction "E_1") (pintype "passive"))
      (node (ref "T62") (pin "1") (pinfunction "E_1") (pintype "passive"))
      (node (ref "T63") (pin "1") (pinfunction "E_1") (pintype "passive"))
      (node (ref "T64") (pin "1") (pinfunction "E_1") (pintype "passive"))
      (node (ref "T65") (pin "1") (pinfunction "E_1") (pintype "passive"))
      (node (ref "T66") (pin "1") (pinfunction "E_1") (pintype "passive"))
      (node (ref "T67") (pin "1") (pinfunction "E_1") (pintype "passive"))
      (node (ref "T68") (pin "1") (pinfunction "E_1") (pintype "passive"))
      (node (ref "T69") (pin "1") (pinfunction "E_1") (pintype "passive"))
      (node (ref "T7") (pin "1") (pinfunction "E_1") (pintype "passive"))
      (node (ref "T70") (pin "1") (pinfunction "E_1") (pintype "passive"))
      (node (ref "T71") (pin "1") (pinfunction "E_1") (pintype "passive"))
      (node (ref "T72") (pin "1") (pinfunction "E_1") (pintype "passive"))
      (node (ref "T73") (pin "1") (pinfunction "E_1") (pintype "passive"))
      (node (ref "T74") (pin "1") (pinfunction "E_1") (pintype "passive"))
      (node (ref "T75") (pin "1") (pinfunction "E_1") (pintype "passive"))
      (node (ref "T76") (pin "1") (pinfunction "E_1") (pintype "passive"))
      (node (ref "T77") (pin "1") (pinfunction "E_1") (pintype "passive"))
      (node (ref "T78") (pin "1") (pinfunction "E_1") (pintype "passive"))
      (node (ref "T79") (pin "1") (pinfunction "E_1") (pintype "passive"))
      (node (ref "T8") (pin "1") (pinfunction "E_1") (pintype "passive"))
      (node (ref "T80") (pin "1") (pinfunction "E_1") (pintype "passive"))
      (node (ref "T81") (pin "1") (pinfunction "E_1") (pintype "passive"))
      (node (ref "T82") (pin "1") (pinfunction "E_1") (pintype "passive"))
      (node (ref "T83") (pin "1") (pinfunction "E_1") (pintype "passive"))
      (node (ref "T84") (pin "1") (pinfunction "E_1") (pintype "passive"))
      (node (ref "T85") (pin "1") (pinfunction "E_1") (pintype "passive"))
      (node (ref "T86") (pin "1") (pinfunction "E_1") (pintype "passive"))
      (node (ref "T87") (pin "1") (pinfunction "E_1") (pintype "passive"))
      (node (ref "T88") (pin "1") (pinfunction "E_1") (pintype "passive"))
      (node (ref "T89") (pin "1") (pinfunction "E_1") (pintype "passive"))
      (node (ref "T9") (pin "1") (pinfunction "E_1") (pintype "passive"))
    )
    (net (code "25") (name "IF0") (class "Default")
      (node (ref "C40") (pin "24") (pinfunction "24_24") (pintype "passive"))
      (node (ref "C40BOT") (pin "14") (pinfunction "1_14") (pintype "passive"))
      (node (ref "T4") (pin "2") (pinfunction "B_2") (pintype "passive"))
    )
    (net (code "26") (name "IF1") (class "Default")
      (node (ref "C40") (pin "25") (pinfunction "25_25") (pintype "passive"))
      (node (ref "C40TOP") (pin "14") (pinfunction "1_14") (pintype "passive"))
      (node (ref "T5") (pin "2") (pinfunction "B_2") (pintype "passive"))
    )
    (net (code "27") (name "IF2") (class "Default")
      (node (ref "C40") (pin "34") (pinfunction "34_34") (pintype "passive"))
      (node (ref "C40BOT") (pin "19") (pinfunction "1_19") (pintype "passive"))
      (node (ref "T6") (pin "2") (pinfunction "B_2") (pintype "passive"))
    )
    (net (code "28") (name "ION") (class "Default")
      (node (ref "D40") (pin "34") (pinfunction "34_34") (pintype "passive"))
      (node (ref "F40BOT") (pin "19") (pinfunction "1_19") (pintype "passive"))
      (node (ref "T73") (pin "2") (pinfunction "B_2") (pintype "passive"))
    )
    (net (code "29") (name "IOT") (class "Default")
      (node (ref "D40") (pin "23") (pinfunction "23_23") (pintype "passive"))
      (node (ref "F40TOP") (pin "13") (pinfunction "1_13") (pintype "passive"))
      (node (ref "T88") (pin "2") (pinfunction "B_2") (pintype "passive"))
    )
    (net (code "30") (name "ISZ") (class "Default")
      (node (ref "D40") (pin "6") (pinfunction "6_6") (pintype "passive"))
      (node (ref "F40BOT") (pin "3") (pinfunction "1_3") (pintype "passive"))
      (node (ref "T84") (pin "2") (pinfunction "B_2") (pintype "passive"))
    )
    (net (code "31") (name "JMP") (class "Default")
      (node (ref "D40") (pin "12") (pinfunction "12_12") (pintype "passive"))
      (node (ref "F40BOT") (pin "6") (pinfunction "1_6") (pintype "passive"))
      (node (ref "T87") (pin "2") (pinfunction "B_2") (pintype "passive"))
    )
    (net (code "32") (name "JMS") (class "Default")
      (node (ref "D40") (pin "10") (pinfunction "10_10") (pintype "passive"))
      (node (ref "F40BOT") (pin "5") (pinfunction "1_5") (pintype "passive"))
      (node (ref "T86") (pin "2") (pinfunction "B_2") (pintype "passive"))
    )
    (net (code "33") (name "LINK") (class "Default")
      (node (ref "C40") (pin "28") (pinfunction "28_28") (pintype "passive"))
      (node (ref "C40BOT") (pin "16") (pinfunction "1_16") (pintype "passive"))
      (node (ref "T72") (pin "2") (pinfunction "B_2") (pintype "passive"))
    )
    (net (code "34") (name "MA0") (class "Default")
      (node (ref "D40TOP") (pin "2") (pinfunction "1_2") (pintype "passive"))
      (node (ref "E40") (pin "3") (pinfunction "3_3") (pintype "passive"))
      (node (ref "T19") (pin "2") (pinfunction "B_2") (pintype "passive"))
    )
    (net (code "35") (name "MA1") (class "Default")
      (node (ref "D40BOT") (pin "4") (pinfunction "1_4") (pintype "passive"))
      (node (ref "E40") (pin "8") (pinfunction "8_8") (pintype "passive"))
      (node (ref "T20") (pin "2") (pinfunction "B_2") (pintype "passive"))
    )
    (net (code "36") (name "MA2") (class "Default")
      (node (ref "D40TOP") (pin "7") (pinfunction "1_7") (pintype "passive"))
      (node (ref "E40") (pin "13") (pinfunction "13_13") (pintype "passive"))
      (node (ref "T21") (pin "2") (pinfunction "B_2") (pintype "passive"))
    )
    (net (code "37") (name "MA3") (class "Default")
      (node (ref "D40BOT") (pin "12") (pinfunction "1_12") (pintype "passive"))
      (node (ref "E40") (pin "22") (pinfunction "22_22") (pintype "passive"))
      (node (ref "T22") (pin "2") (pinfunction "B_2") (pintype "passive"))
    )
    (net (code "38") (name "MA4") (class "Default")
      (node (ref "D40TOP") (pin "15") (pinfunction "1_15") (pintype "passive"))
      (node (ref "E40") (pin "27") (pinfunction "27_27") (pintype "passive"))
      (node (ref "T23") (pin "2") (pinfunction "B_2") (pintype "passive"))
    )
    (net (code "39") (name "MA5") (class "Default")
      (node (ref "D40BOT") (pin "18") (pinfunction "1_18") (pintype "passive"))
      (node (ref "E40") (pin "32") (pinfunction "32_32") (pintype "passive"))
      (node (ref "T24") (pin "2") (pinfunction "B_2") (pintype "passive"))
    )
    (net (code "40") (name "MA6") (class "Default")
      (node (ref "E40TOP") (pin "2") (pinfunction "1_2") (pintype "passive"))
      (node (ref "F40") (pin "3") (pinfunction "3_3") (pintype "passive"))
      (node (ref "T25") (pin "2") (pinfunction "B_2") (pintype "passive"))
    )
    (net (code "41") (name "MA7") (class "Default")
      (node (ref "E40BOT") (pin "4") (pinfunction "1_4") (pintype "passive"))
      (node (ref "F40") (pin "8") (pinfunction "8_8") (pintype "passive"))
      (node (ref "T26") (pin "2") (pinfunction "B_2") (pintype "passive"))
    )
    (net (code "42") (name "MA8") (class "Default")
      (node (ref "E40TOP") (pin "7") (pinfunction "1_7") (pintype "passive"))
      (node (ref "F40") (pin "13") (pinfunction "13_13") (pintype "passive"))
      (node (ref "T27") (pin "2") (pinfunction "B_2") (pintype "passive"))
    )
    (net (code "43") (name "MA9") (class "Default")
      (node (ref "E40BOT") (pin "12") (pinfunction "1_12") (pintype "passive"))
      (node (ref "F40") (pin "22") (pinfunction "22_22") (pintype "passive"))
      (node (ref "T28") (pin "2") (pinfunction "B_2") (pintype "passive"))
    )
    (net (code "44") (name "MA10") (class "Default")
      (node (ref "E40TOP") (pin "15") (pinfunction "1_15") (pintype "passive"))
      (node (ref "F40") (pin "27") (pinfunction "27_27") (pintype "passive"))
      (node (ref "T29") (pin "2") (pinfunction "B_2") (pintype "passive"))
    )
    (net (code "45") (name "MA11") (class "Default")
      (node (ref "E40BOT") (pin "18") (pinfunction "1_18") (pintype "passive"))
      (node (ref "F40") (pin "32") (pinfunction "32_32") (pintype "passive"))
      (node (ref "T30") (pin "2") (pinfunction "B_2") (pintype "passive"))
    )
    (net (code "46") (name "MB0") (class "Default")
      (node (ref "D40TOP") (pin "3") (pinfunction "1_3") (pintype "passive"))
      (node (ref "E40") (pin "5") (pinfunction "5_5") (pintype "passive"))
      (node (ref "T31") (pin "2") (pinfunction "B_2") (pintype "passive"))
    )
    (net (code "47") (name "MB1") (class "Default")
      (node (ref "D40BOT") (pin "3") (pinfunction "1_3") (pintype "passive"))
      (node (ref "E40") (pin "6") (pinfunction "6_6") (pintype "passive"))
      (node (ref "T32") (pin "2") (pinfunction "B_2") (pintype "passive"))
    )
    (net (code "48") (name "MB2") (class "Default")
      (node (ref "D40TOP") (pin "8") (pinfunction "1_8") (pintype "passive"))
      (node (ref "E40") (pin "15") (pinfunction "15_15") (pintype "passive"))
      (node (ref "T33") (pin "2") (pinfunction "B_2") (pintype "passive"))
    )
    (net (code "49") (name "MB3") (class "Default")
      (node (ref "D40BOT") (pin "11") (pinfunction "1_11") (pintype "passive"))
      (node (ref "E40") (pin "16") (pinfunction "16_16") (pintype "passive"))
      (node (ref "T34") (pin "2") (pinfunction "B_2") (pintype "passive"))
    )
    (net (code "50") (name "MB4") (class "Default")
      (node (ref "D40TOP") (pin "16") (pinfunction "1_16") (pintype "passive"))
      (node (ref "E40") (pin "29") (pinfunction "29_29") (pintype "passive"))
      (node (ref "T35") (pin "2") (pinfunction "B_2") (pintype "passive"))
    )
    (net (code "51") (name "MB5") (class "Default")
      (node (ref "D40BOT") (pin "17") (pinfunction "1_17") (pintype "passive"))
      (node (ref "E40") (pin "30") (pinfunction "30_30") (pintype "passive"))
      (node (ref "T36") (pin "2") (pinfunction "B_2") (pintype "passive"))
    )
    (net (code "52") (name "MB6") (class "Default")
      (node (ref "E40TOP") (pin "3") (pinfunction "1_3") (pintype "passive"))
      (node (ref "F40") (pin "5") (pinfunction "5_5") (pintype "passive"))
      (node (ref "T37") (pin "2") (pinfunction "B_2") (pintype "passive"))
    )
    (net (code "53") (name "MB7") (class "Default")
      (node (ref "E40BOT") (pin "3") (pinfunction "1_3") (pintype "passive"))
      (node (ref "F40") (pin "6") (pinfunction "6_6") (pintype "passive"))
      (node (ref "T38") (pin "2") (pinfunction "B_2") (pintype "passive"))
    )
    (net (code "54") (name "MB8") (class "Default")
      (node (ref "E40TOP") (pin "8") (pinfunction "1_8") (pintype "passive"))
      (node (ref "F40") (pin "15") (pinfunction "15_15") (pintype "passive"))
      (node (ref "T39") (pin "2") (pinfunction "B_2") (pintype "passive"))
    )
    (net (code "55") (name "MB9") (class "Default")
      (node (ref "E40BOT") (pin "11") (pinfunction "1_11") (pintype "passive"))
      (node (ref "F40") (pin "16") (pinfunction "16_16") (pintype "passive"))
      (node (ref "T40") (pin "2") (pinfunction "B_2") (pintype "passive"))
    )
    (net (code "56") (name "MB10") (class "Default")
      (node (ref "E40TOP") (pin "16") (pinfunction "1_16") (pintype "passive"))
      (node (ref "F40") (pin "29") (pinfunction "29_29") (pintype "passive"))
      (node (ref "T41") (pin "2") (pinfunction "B_2") (pintype "passive"))
    )
    (net (code "57") (name "MB11") (class "Default")
      (node (ref "E40BOT") (pin "17") (pinfunction "1_17") (pintype "passive"))
      (node (ref "F40") (pin "30") (pinfunction "30_30") (pintype "passive"))
      (node (ref "T42") (pin "2") (pinfunction "B_2") (pintype "passive"))
    )
    (net (code "58") (name "MQ0") (class "Default")
      (node (ref "D40TOP") (pin "5") (pinfunction "1_5") (pintype "passive"))
      (node (ref "E40") (pin "9") (pinfunction "9_9") (pintype "passive"))
      (node (ref "T55") (pin "2") (pinfunction "B_2") (pintype "passive"))
    )
    (net (code "59") (name "MQ1") (class "Default")
      (node (ref "D40BOT") (pin "1") (pinfunction "1_1") (pintype "passive"))
      (node (ref "E40") (pin "2") (pinfunction "2_2") (pintype "passive"))
      (node (ref "T56") (pin "2") (pinfunction "B_2") (pintype "passive"))
    )
    (net (code "60") (name "MQ2") (class "Default")
      (node (ref "D40TOP") (pin "13") (pinfunction "1_13") (pintype "passive"))
      (node (ref "E40") (pin "23") (pinfunction "23_23") (pintype "passive"))
      (node (ref "T57") (pin "2") (pinfunction "B_2") (pintype "passive"))
    )
    (net (code "61") (name "MQ3") (class "Default")
      (node (ref "D40BOT") (pin "6") (pinfunction "1_6") (pintype "passive"))
      (node (ref "E40") (pin "12") (pinfunction "12_12") (pintype "passive"))
      (node (ref "T58") (pin "2") (pinfunction "B_2") (pintype "passive"))
    )
    (net (code "62") (name "MQ4") (class "Default")
      (node (ref "D40TOP") (pin "18") (pinfunction "1_18") (pintype "passive"))
      (node (ref "E40") (pin "33") (pinfunction "33_33") (pintype "passive"))
      (node (ref "T59") (pin "2") (pinfunction "B_2") (pintype "passive"))
    )
    (net (code "63") (name "MQ5") (class "Default")
      (node (ref "D40BOT") (pin "15") (pinfunction "1_15") (pintype "passive"))
      (node (ref "E40") (pin "26") (pinfunction "26_26") (pintype "passive"))
      (node (ref "T60") (pin "2") (pinfunction "B_2") (pintype "passive"))
    )
    (net (code "64") (name "MQ6") (class "Default")
      (node (ref "E40TOP") (pin "5") (pinfunction "1_5") (pintype "passive"))
      (node (ref "F40") (pin "9") (pinfunction "9_9") (pintype "passive"))
      (node (ref "T61") (pin "2") (pinfunction "B_2") (pintype "passive"))
    )
    (net (code "65") (name "MQ7") (class "Default")
      (node (ref "E40BOT") (pin "1") (pinfunction "1_1") (pintype "passive"))
      (node (ref "F40") (pin "2") (pinfunction "2_2") (pintype "passive"))
      (node (ref "T62") (pin "2") (pinfunction "B_2") (pintype "passive"))
    )
    (net (code "66") (name "MQ8") (class "Default")
      (node (ref "E40TOP") (pin "13") (pinfunction "1_13") (pintype "passive"))
      (node (ref "F40") (pin "23") (pinfunction "23_23") (pintype "passive"))
      (node (ref "T63") (pin "2") (pinfunction "B_2") (pintype "passive"))
    )
    (net (code "67") (name "MQ9") (class "Default")
      (node (ref "E40BOT") (pin "6") (pinfunction "1_6") (pintype "passive"))
      (node (ref "F40") (pin "12") (pinfunction "12_12") (pintype "passive"))
      (node (ref "T64") (pin "2") (pinfunction "B_2") (pintype "passive"))
    )
    (net (code "68") (name "MQ10") (class "Default")
      (node (ref "E40TOP") (pin "18") (pinfunction "1_18") (pintype "passive"))
      (node (ref "F40") (pin "33") (pinfunction "33_33") (pintype "passive"))
      (node (ref "T65") (pin "2") (pinfunction "B_2") (pintype "passive"))
    )
    (net (code "69") (name "MQ11") (class "Default")
      (node (ref "E40BOT") (pin "15") (pinfunction "1_15") (pintype "passive"))
      (node (ref "F40") (pin "26") (pinfunction "26_26") (pintype "passive"))
      (node (ref "T66") (pin "2") (pinfunction "B_2") (pintype "passive"))
    )
    (net (code "70") (name "Net-(T1-C)") (class "Default")
      (node (ref "DF0") (pin "B") (pinfunction "B_B") (pintype "passive"))
      (node (ref "T1") (pin "3") (pinfunction "C_3") (pintype "passive"))
    )
    (net (code "71") (name "Net-(T2-C)") (class "Default")
      (node (ref "DF1") (pin "B") (pinfunction "B_B") (pintype "passive"))
      (node (ref "T2") (pin "3") (pinfunction "C_3") (pintype "passive"))
    )
    (net (code "72") (name "Net-(T3-C)") (class "Default")
      (node (ref "DF2") (pin "B") (pinfunction "B_B") (pintype "passive"))
      (node (ref "T3") (pin "3") (pinfunction "C_3") (pintype "passive"))
    )
    (net (code "73") (name "Net-(T4-C)") (class "Default")
      (node (ref "IF0") (pin "B") (pinfunction "B_B") (pintype "passive"))
      (node (ref "T4") (pin "3") (pinfunction "C_3") (pintype "passive"))
    )
    (net (code "74") (name "Net-(T5-C)") (class "Default")
      (node (ref "IF1") (pin "B") (pinfunction "B_B") (pintype "passive"))
      (node (ref "T5") (pin "3") (pinfunction "C_3") (pintype "passive"))
    )
    (net (code "75") (name "Net-(T6-C)") (class "Default")
      (node (ref "IF2") (pin "B") (pinfunction "B_B") (pintype "passive"))
      (node (ref "T6") (pin "3") (pinfunction "C_3") (pintype "passive"))
    )
    (net (code "76") (name "Net-(T7-C)") (class "Default")
      (node (ref "PC0") (pin "B") (pinfunction "B_B") (pintype "passive"))
      (node (ref "T7") (pin "3") (pinfunction "C_3") (pintype "passive"))
    )
    (net (code "77") (name "Net-(T8-C)") (class "Default")
      (node (ref "PC1") (pin "B") (pinfunction "B_B") (pintype "passive"))
      (node (ref "T8") (pin "3") (pinfunction "C_3") (pintype "passive"))
    )
    (net (code "78") (name "Net-(T9-C)") (class "Default")
      (node (ref "PC2") (pin "B") (pinfunction "B_B") (pintype "passive"))
      (node (ref "T9") (pin "3") (pinfunction "C_3") (pintype "passive"))
    )
    (net (code "79") (name "Net-(T10-C)") (class "Default")
      (node (ref "PC3") (pin "B") (pinfunction "B_B") (pintype "passive"))
      (node (ref "T10") (pin "3") (pinfunction "C_3") (pintype "passive"))
    )
    (net (code "80") (name "Net-(T11-C)") (class "Default")
      (node (ref "PC4") (pin "B") (pinfunction "B_B") (pintype "passive"))
      (node (ref "T11") (pin "3") (pinfunction "C_3") (pintype "passive"))
    )
    (net (code "81") (name "Net-(T12-C)") (class "Default")
      (node (ref "PC5") (pin "B") (pinfunction "B_B") (pintype "passive"))
      (node (ref "T12") (pin "3") (pinfunction "C_3") (pintype "passive"))
    )
    (net (code "82") (name "Net-(T13-C)") (class "Default")
      (node (ref "PC6") (pin "B") (pinfunction "B_B") (pintype "passive"))
      (node (ref "T13") (pin "3") (pinfunction "C_3") (pintype "passive"))
    )
    (net (code "83") (name "Net-(T14-C)") (class "Default")
      (node (ref "PC7") (pin "B") (pinfunction "B_B") (pintype "passive"))
      (node (ref "T14") (pin "3") (pinfunction "C_3") (pintype "passive"))
    )
    (net (code "84") (name "Net-(T15-C)") (class "Default")
      (node (ref "PC8") (pin "B") (pinfunction "B_B") (pintype "passive"))
      (node (ref "T15") (pin "3") (pinfunction "C_3") (pintype "passive"))
    )
    (net (code "85") (name "Net-(T16-C)") (class "Default")
      (node (ref "PC9") (pin "B") (pinfunction "B_B") (pintype "passive"))
      (node (ref "T16") (pin "3") (pinfunction "C_3") (pintype "passive"))
    )
    (net (code "86") (name "Net-(T17-C)") (class "Default")
      (node (ref "PC10") (pin "B") (pinfunction "B_B") (pintype "passive"))
      (node (ref "T17") (pin "3") (pinfunction "C_3") (pintype "passive"))
    )
    (net (code "87") (name "Net-(T18-C)") (class "Default")
      (node (ref "PC11") (pin "B") (pinfunction "B_B") (pintype "passive"))
      (node (ref "T18") (pin "3") (pinfunction "C_3") (pintype "passive"))
    )
    (net (code "88") (name "Net-(T19-C)") (class "Default")
      (node (ref "MA0") (pin "B") (pinfunction "B_B") (pintype "passive"))
      (node (ref "T19") (pin "3") (pinfunction "C_3") (pintype "passive"))
    )
    (net (code "89") (name "Net-(T20-C)") (class "Default")
      (node (ref "MA1") (pin "B") (pinfunction "B_B") (pintype "passive"))
      (node (ref "T20") (pin "3") (pinfunction "C_3") (pintype "passive"))
    )
    (net (code "90") (name "Net-(T21-C)") (class "Default")
      (node (ref "MA2") (pin "B") (pinfunction "B_B") (pintype "passive"))
      (node (ref "T21") (pin "3") (pinfunction "C_3") (pintype "passive"))
    )
    (net (code "91") (name "Net-(T22-C)") (class "Default")
      (node (ref "MA3") (pin "B") (pinfunction "B_B") (pintype "passive"))
      (node (ref "T22") (pin "3") (pinfunction "C_3") (pintype "passive"))
    )
    (net (code "92") (name "Net-(T23-C)") (class "Default")
      (node (ref "MA4") (pin "B") (pinfunction "B_B") (pintype "passive"))
      (node (ref "T23") (pin "3") (pinfunction "C_3") (pintype "passive"))
    )
    (net (code "93") (name "Net-(T24-C)") (class "Default")
      (node (ref "MA5") (pin "B") (pinfunction "B_B") (pintype "passive"))
      (node (ref "T24") (pin "3") (pinfunction "C_3") (pintype "passive"))
    )
    (net (code "94") (name "Net-(T25-C)") (class "Default")
      (node (ref "MA6") (pin "B") (pinfunction "B_B") (pintype "passive"))
      (node (ref "T25") (pin "3") (pinfunction "C_3") (pintype "passive"))
    )
    (net (code "95") (name "Net-(T26-C)") (class "Default")
      (node (ref "MA7") (pin "B") (pinfunction "B_B") (pintype "passive"))
      (node (ref "T26") (pin "3") (pinfunction "C_3") (pintype "passive"))
    )
    (net (code "96") (name "Net-(T27-C)") (class "Default")
      (node (ref "MA8") (pin "B") (pinfunction "B_B") (pintype "passive"))
      (node (ref "T27") (pin "3") (pinfunction "C_3") (pintype "passive"))
    )
    (net (code "97") (name "Net-(T28-C)") (class "Default")
      (node (ref "MA9") (pin "B") (pinfunction "B_B") (pintype "passive"))
      (node (ref "T28") (pin "3") (pinfunction "C_3") (pintype "passive"))
    )
    (net (code "98") (name "Net-(T29-C)") (class "Default")
      (node (ref "MA10") (pin "B") (pinfunction "B_B") (pintype "passive"))
      (node (ref "T29") (pin "3") (pinfunction "C_3") (pintype "passive"))
    )
    (net (code "99") (name "Net-(T30-C)") (class "Default")
      (node (ref "MA11") (pin "B") (pinfunction "B_B") (pintype "passive"))
      (node (ref "T30") (pin "3") (pinfunction "C_3") (pintype "passive"))
    )
    (net (code "100") (name "Net-(T31-C)") (class "Default")
      (node (ref "MB0") (pin "B") (pinfunction "B_B") (pintype "passive"))
      (node (ref "T31") (pin "3") (pinfunction "C_3") (pintype "passive"))
    )
    (net (code "101") (name "Net-(T32-C)") (class "Default")
      (node (ref "MB1") (pin "B") (pinfunction "B_B") (pintype "passive"))
      (node (ref "T32") (pin "3") (pinfunction "C_3") (pintype "passive"))
    )
    (net (code "102") (name "Net-(T33-C)") (class "Default")
      (node (ref "MB2") (pin "B") (pinfunction "B_B") (pintype "passive"))
      (node (ref "T33") (pin "3") (pinfunction "C_3") (pintype "passive"))
    )
    (net (code "103") (name "Net-(T34-C)") (class "Default")
      (node (ref "MB3") (pin "B") (pinfunction "B_B") (pintype "passive"))
      (node (ref "T34") (pin "3") (pinfunction "C_3") (pintype "passive"))
    )
    (net (code "104") (name "Net-(T35-C)") (class "Default")
      (node (ref "MB4") (pin "B") (pinfunction "B_B") (pintype "passive"))
      (node (ref "T35") (pin "3") (pinfunction "C_3") (pintype "passive"))
    )
    (net (code "105") (name "Net-(T36-C)") (class "Default")
      (node (ref "MB5") (pin "B") (pinfunction "B_B") (pintype "passive"))
      (node (ref "T36") (pin "3") (pinfunction "C_3") (pintype "passive"))
    )
    (net (code "106") (name "Net-(T37-C)") (class "Default")
      (node (ref "MB6") (pin "B") (pinfunction "B_B") (pintype "passive"))
      (node (ref "T37") (pin "3") (pinfunction "C_3") (pintype "passive"))
    )
    (net (code "107") (name "Net-(T38-C)") (class "Default")
      (node (ref "MB7") (pin "B") (pinfunction "B_B") (pintype "passive"))
      (node (ref "T38") (pin "3") (pinfunction "C_3") (pintype "passive"))
    )
    (net (code "108") (name "Net-(T39-C)") (class "Default")
      (node (ref "MB8") (pin "B") (pinfunction "B_B") (pintype "passive"))
      (node (ref "T39") (pin "3") (pinfunction "C_3") (pintype "passive"))
    )
    (net (code "109") (name "Net-(T40-C)") (class "Default")
      (node (ref "MB9") (pin "B") (pinfunction "B_B") (pintype "passive"))
      (node (ref "T40") (pin "3") (pinfunction "C_3") (pintype "passive"))
    )
    (net (code "110") (name "Net-(T41-C)") (class "Default")
      (node (ref "MB10") (pin "B") (pinfunction "B_B") (pintype "passive"))
      (node (ref "T41") (pin "3") (pinfunction "C_3") (pintype "passive"))
    )
    (net (code "111") (name "Net-(T42-C)") (class "Default")
      (node (ref "MB11") (pin "B") (pinfunction "B_B") (pintype "passive"))
      (node (ref "T42") (pin "3") (pinfunction "C_3") (pintype "passive"))
    )
    (net (code "112") (name "Net-(T43-C)") (class "Default")
      (node (ref "AC0") (pin "B") (pinfunction "B_B") (pintype "passive"))
      (node (ref "T43") (pin "3") (pinfunction "C_3") (pintype "passive"))
    )
    (net (code "113") (name "Net-(T44-C)") (class "Default")
      (node (ref "AC1") (pin "B") (pinfunction "B_B") (pintype "passive"))
      (node (ref "T44") (pin "3") (pinfunction "C_3") (pintype "passive"))
    )
    (net (code "114") (name "Net-(T45-C)") (class "Default")
      (node (ref "AC2") (pin "B") (pinfunction "B_B") (pintype "passive"))
      (node (ref "T45") (pin "3") (pinfunction "C_3") (pintype "passive"))
    )
    (net (code "115") (name "Net-(T46-C)") (class "Default")
      (node (ref "AC3") (pin "B") (pinfunction "B_B") (pintype "passive"))
      (node (ref "T46") (pin "3") (pinfunction "C_3") (pintype "passive"))
    )
    (net (code "116") (name "Net-(T47-C)") (class "Default")
      (node (ref "AC4") (pin "B") (pinfunction "B_B") (pintype "passive"))
      (node (ref "T47") (pin "3") (pinfunction "C_3") (pintype "passive"))
    )
    (net (code "117") (name "Net-(T48-C)") (class "Default")
      (node (ref "AC5") (pin "B") (pinfunction "B_B") (pintype "passive"))
      (node (ref "T48") (pin "3") (pinfunction "C_3") (pintype "passive"))
    )
    (net (code "118") (name "Net-(T49-C)") (class "Default")
      (node (ref "AC6") (pin "B") (pinfunction "B_B") (pintype "passive"))
      (node (ref "T49") (pin "3") (pinfunction "C_3") (pintype "passive"))
    )
    (net (code "119") (name "Net-(T50-C)") (class "Default")
      (node (ref "AC7") (pin "B") (pinfunction "B_B") (pintype "passive"))
      (node (ref "T50") (pin "3") (pinfunction "C_3") (pintype "passive"))
    )
    (net (code "120") (name "Net-(T51-C)") (class "Default")
      (node (ref "AC8") (pin "B") (pinfunction "B_B") (pintype "passive"))
      (node (ref "T51") (pin "3") (pinfunction "C_3") (pintype "passive"))
    )
    (net (code "121") (name "Net-(T52-C)") (class "Default")
      (node (ref "AC9") (pin "B") (pinfunction "B_B") (pintype "passive"))
      (node (ref "T52") (pin "3") (pinfunction "C_3") (pintype "passive"))
    )
    (net (code "122") (name "Net-(T53-C)") (class "Default")
      (node (ref "AC10") (pin "B") (pinfunction "B_B") (pintype "passive"))
      (node (ref "T53") (pin "3") (pinfunction "C_3") (pintype "passive"))
    )
    (net (code "123") (name "Net-(T54-C)") (class "Default")
      (node (ref "AC11") (pin "B") (pinfunction "B_B") (pintype "passive"))
      (node (ref "T54") (pin "3") (pinfunction "C_3") (pintype "passive"))
    )
    (net (code "124") (name "Net-(T55-C)") (class "Default")
      (node (ref "MQ0") (pin "B") (pinfunction "B_B") (pintype "passive"))
      (node (ref "T55") (pin "3") (pinfunction "C_3") (pintype "passive"))
    )
    (net (code "125") (name "Net-(T56-C)") (class "Default")
      (node (ref "MQ1") (pin "B") (pinfunction "B_B") (pintype "passive"))
      (node (ref "T56") (pin "3") (pinfunction "C_3") (pintype "passive"))
    )
    (net (code "126") (name "Net-(T57-C)") (class "Default")
      (node (ref "MQ2") (pin "B") (pinfunction "B_B") (pintype "passive"))
      (node (ref "T57") (pin "3") (pinfunction "C_3") (pintype "passive"))
    )
    (net (code "127") (name "Net-(T58-C)") (class "Default")
      (node (ref "MQ3") (pin "B") (pinfunction "B_B") (pintype "passive"))
      (node (ref "T58") (pin "3") (pinfunction "C_3") (pintype "passive"))
    )
    (net (code "128") (name "Net-(T59-C)") (class "Default")
      (node (ref "MQ4") (pin "B") (pinfunction "B_B") (pintype "passive"))
      (node (ref "T59") (pin "3") (pinfunction "C_3") (pintype "passive"))
    )
    (net (code "129") (name "Net-(T60-C)") (class "Default")
      (node (ref "MQ5") (pin "B") (pinfunction "B_B") (pintype "passive"))
      (node (ref "T60") (pin "3") (pinfunction "C_3") (pintype "passive"))
    )
    (net (code "130") (name "Net-(T61-C)") (class "Default")
      (node (ref "MQ6") (pin "B") (pinfunction "B_B") (pintype "passive"))
      (node (ref "T61") (pin "3") (pinfunction "C_3") (pintype "passive"))
    )
    (net (code "131") (name "Net-(T62-C)") (class "Default")
      (node (ref "MQ7") (pin "B") (pinfunction "B_B") (pintype "passive"))
      (node (ref "T62") (pin "3") (pinfunction "C_3") (pintype "passive"))
    )
    (net (code "132") (name "Net-(T63-C)") (class "Default")
      (node (ref "MQ8") (pin "B") (pinfunction "B_B") (pintype "passive"))
      (node (ref "T63") (pin "3") (pinfunction "C_3") (pintype "passive"))
    )
    (net (code "133") (name "Net-(T64-C)") (class "Default")
      (node (ref "MQ9") (pin "B") (pinfunction "B_B") (pintype "passive"))
      (node (ref "T64") (pin "3") (pinfunction "C_3") (pintype "passive"))
    )
    (net (code "134") (name "Net-(T65-C)") (class "Default")
      (node (ref "MQ10") (pin "B") (pinfunction "B_B") (pintype "passive"))
      (node (ref "T65") (pin "3") (pinfunction "C_3") (pintype "passive"))
    )
    (net (code "135") (name "Net-(T66-C)") (class "Default")
      (node (ref "MQ11") (pin "B") (pinfunction "B_B") (pintype "passive"))
      (node (ref "T66") (pin "3") (pinfunction "C_3") (pintype "passive"))
    )
    (net (code "136") (name "Net-(T67-C)") (class "Default")
      (node (ref "SC0") (pin "B") (pinfunction "B_B") (pintype "passive"))
      (node (ref "T67") (pin "3") (pinfunction "C_3") (pintype "passive"))
    )
    (net (code "137") (name "Net-(T68-C)") (class "Default")
      (node (ref "SC1") (pin "B") (pinfunction "B_B") (pintype "passive"))
      (node (ref "T68") (pin "3") (pinfunction "C_3") (pintype "passive"))
    )
    (net (code "138") (name "Net-(T69-C)") (class "Default")
      (node (ref "SC2") (pin "B") (pinfunction "B_B") (pintype "passive"))
      (node (ref "T69") (pin "3") (pinfunction "C_3") (pintype "passive"))
    )
    (net (code "139") (name "Net-(T70-C)") (class "Default")
      (node (ref "SC3") (pin "B") (pinfunction "B_B") (pintype "passive"))
      (node (ref "T70") (pin "3") (pinfunction "C_3") (pintype "passive"))
    )
    (net (code "140") (name "Net-(T71-C)") (class "Default")
      (node (ref "SC4") (pin "B") (pinfunction "B_B") (pintype "passive"))
      (node (ref "T71") (pin "3") (pinfunction "C_3") (pintype "passive"))
    )
    (net (code "141") (name "Net-(T72-C)") (class "Default")
      (node (ref "LINK") (pin "B") (pinfunction "B_B") (pintype "passive"))
      (node (ref "T72") (pin "3") (pinfunction "C_3") (pintype "passive"))
    )
    (net (code "142") (name "Net-(T73-C)") (class "Default")
      (node (ref "ION") (pin "B") (pinfunction "B_B") (pintype "passive"))
      (node (ref "T73") (pin "3") (pinfunction "C_3") (pintype "passive"))
    )
    (net (code "143") (name "Net-(T74-C)") (class "Default")
      (node (ref "PAUSE") (pin "B") (pinfunction "B_B") (pintype "passive"))
      (node (ref "T74") (pin "3") (pinfunction "C_3") (pintype "passive"))
    )
    (net (code "144") (name "Net-(T75-C)") (class "Default")
      (node (ref "RUN") (pin "B") (pinfunction "B_B") (pintype "passive"))
      (node (ref "T75") (pin "3") (pinfunction "C_3") (pintype "passive"))
    )
    (net (code "145") (name "Net-(T76-C)") (class "Default")
      (node (ref "FETCH") (pin "B") (pinfunction "B_B") (pintype "passive"))
      (node (ref "T76") (pin "3") (pinfunction "C_3") (pintype "passive"))
    )
    (net (code "146") (name "Net-(T77-C)") (class "Default")
      (node (ref "EXECUTE") (pin "B") (pinfunction "B_B") (pintype "passive"))
      (node (ref "T77") (pin "3") (pinfunction "C_3") (pintype "passive"))
    )
    (net (code "147") (name "Net-(T78-C)") (class "Default")
      (node (ref "DEFER") (pin "B") (pinfunction "B_B") (pintype "passive"))
      (node (ref "T78") (pin "3") (pinfunction "C_3") (pintype "passive"))
    )
    (net (code "148") (name "Net-(T79-C)") (class "Default")
      (node (ref "T79") (pin "3") (pinfunction "C_3") (pintype "passive"))
      (node (ref "WORDCOUNT") (pin "B") (pinfunction "B_B") (pintype "passive"))
    )
    (net (code "149") (name "Net-(T80-C)") (class "Default")
      (node (ref "CURRENTADDRESS") (pin "B") (pinfunction "B_B") (pintype "passive"))
      (node (ref "T80") (pin "3") (pinfunction "C_3") (pintype "passive"))
    )
    (net (code "150") (name "Net-(T81-C)") (class "Default")
      (node (ref "BREAK") (pin "B") (pinfunction "B_B") (pintype "passive"))
      (node (ref "T81") (pin "3") (pinfunction "C_3") (pintype "passive"))
    )
    (net (code "151") (name "Net-(T82-C)") (class "Default")
      (node (ref "AND") (pin "B") (pinfunction "B_B") (pintype "passive"))
      (node (ref "T82") (pin "3") (pinfunction "C_3") (pintype "passive"))
    )
    (net (code "152") (name "Net-(T83-C)") (class "Default")
      (node (ref "T83") (pin "3") (pinfunction "C_3") (pintype "passive"))
      (node (ref "TAD") (pin "B") (pinfunction "B_B") (pintype "passive"))
    )
    (net (code "153") (name "Net-(T84-C)") (class "Default")
      (node (ref "ISZ") (pin "B") (pinfunction "B_B") (pintype "passive"))
      (node (ref "T84") (pin "3") (pinfunction "C_3") (pintype "passive"))
    )
    (net (code "154") (name "Net-(T85-C)") (class "Default")
      (node (ref "DCA") (pin "B") (pinfunction "B_B") (pintype "passive"))
      (node (ref "T85") (pin "3") (pinfunction "C_3") (pintype "passive"))
    )
    (net (code "155") (name "Net-(T86-C)") (class "Default")
      (node (ref "JMS") (pin "B") (pinfunction "B_B") (pintype "passive"))
      (node (ref "T86") (pin "3") (pinfunction "C_3") (pintype "passive"))
    )
    (net (code "156") (name "Net-(T87-C)") (class "Default")
      (node (ref "JMP") (pin "B") (pinfunction "B_B") (pintype "passive"))
      (node (ref "T87") (pin "3") (pinfunction "C_3") (pintype "passive"))
    )
    (net (code "157") (name "Net-(T88-C)") (class "Default")
      (node (ref "IOT") (pin "B") (pinfunction "B_B") (pintype "passive"))
      (node (ref "T88") (pin "3") (pinfunction "C_3") (pintype "passive"))
    )
    (net (code "158") (name "Net-(T89-C)") (class "Default")
      (node (ref "OPR") (pin "B") (pinfunction "B_B") (pintype "passive"))
      (node (ref "T89") (pin "3") (pinfunction "C_3") (pintype "passive"))
    )
    (net (code "159") (name "OPR") (class "Default")
      (node (ref "D40") (pin "16") (pinfunction "16_16") (pintype "passive"))
      (node (ref "F40BOT") (pin "11") (pinfunction "1_11") (pintype "passive"))
      (node (ref "T89") (pin "2") (pinfunction "B_2") (pintype "passive"))
    )
    (net (code "160") (name "PAUSE") (class "Default")
      (node (ref "D40") (pin "31") (pinfunction "31_31") (pintype "passive"))
      (node (ref "F40TOP") (pin "17") (pinfunction "1_17") (pintype "passive"))
      (node (ref "T74") (pin "2") (pinfunction "B_2") (pintype "passive"))
    )
    (net (code "161") (name "PC0") (class "Default")
      (node (ref "D40TOP") (pin "1") (pinfunction "1_1") (pintype "passive"))
      (node (ref "E40") (pin "1") (pinfunction "1_1") (pintype "passive"))
      (node (ref "T7") (pin "2") (pinfunction "B_2") (pintype "passive"))
    )
    (net (code "162") (name "PC1") (class "Default")
      (node (ref "D40BOT") (pin "5") (pinfunction "1_5") (pintype "passive"))
      (node (ref "E40") (pin "10") (pinfunction "10_10") (pintype "passive"))
      (node (ref "T8") (pin "2") (pinfunction "B_2") (pintype "passive"))
    )
    (net (code "163") (name "PC2") (class "Default")
      (node (ref "D40TOP") (pin "6") (pinfunction "1_6") (pintype "passive"))
      (node (ref "E40") (pin "11") (pinfunction "11_11") (pintype "passive"))
      (node (ref "T9") (pin "2") (pinfunction "B_2") (pintype "passive"))
    )
    (net (code "164") (name "PC3") (class "Default")
      (node (ref "D40BOT") (pin "14") (pinfunction "1_14") (pintype "passive"))
      (node (ref "E40") (pin "24") (pinfunction "24_24") (pintype "passive"))
      (node (ref "T10") (pin "2") (pinfunction "B_2") (pintype "passive"))
    )
    (net (code "165") (name "PC4") (class "Default")
      (node (ref "D40TOP") (pin "14") (pinfunction "1_14") (pintype "passive"))
      (node (ref "E40") (pin "25") (pinfunction "25_25") (pintype "passive"))
      (node (ref "T11") (pin "2") (pinfunction "B_2") (pintype "passive"))
    )
    (net (code "166") (name "PC5") (class "Default")
      (node (ref "D40BOT") (pin "19") (pinfunction "1_19") (pintype "passive"))
      (node (ref "E40") (pin "34") (pinfunction "34_34") (pintype "passive"))
      (node (ref "T12") (pin "2") (pinfunction "B_2") (pintype "passive"))
    )
    (net (code "167") (name "PC6") (class "Default")
      (node (ref "E40TOP") (pin "1") (pinfunction "1_1") (pintype "passive"))
      (node (ref "F40") (pin "1") (pinfunction "1_1") (pintype "passive"))
      (node (ref "T13") (pin "2") (pinfunction "B_2") (pintype "passive"))
    )
    (net (code "168") (name "PC7") (class "Default")
      (node (ref "E40BOT") (pin "5") (pinfunction "1_5") (pintype "passive"))
      (node (ref "F40") (pin "10") (pinfunction "10_10") (pintype "passive"))
      (node (ref "T14") (pin "2") (pinfunction "B_2") (pintype "passive"))
    )
    (net (code "169") (name "PC8") (class "Default")
      (node (ref "E40TOP") (pin "6") (pinfunction "1_6") (pintype "passive"))
      (node (ref "F40") (pin "11") (pinfunction "11_11") (pintype "passive"))
      (node (ref "T15") (pin "2") (pinfunction "B_2") (pintype "passive"))
    )
    (net (code "170") (name "PC9") (class "Default")
      (node (ref "E40BOT") (pin "14") (pinfunction "1_14") (pintype "passive"))
      (node (ref "F40") (pin "24") (pinfunction "24_24") (pintype "passive"))
      (node (ref "T16") (pin "2") (pinfunction "B_2") (pintype "passive"))
    )
    (net (code "171") (name "PC10") (class "Default")
      (node (ref "E40TOP") (pin "14") (pinfunction "1_14") (pintype "passive"))
      (node (ref "F40") (pin "25") (pinfunction "25_25") (pintype "passive"))
      (node (ref "T17") (pin "2") (pinfunction "B_2") (pintype "passive"))
    )
    (net (code "172") (name "PC11") (class "Default")
      (node (ref "E40BOT") (pin "19") (pinfunction "1_19") (pintype "passive"))
      (node (ref "F40") (pin "34") (pinfunction "34_34") (pintype "passive"))
      (node (ref "T18") (pin "2") (pinfunction "B_2") (pintype "passive"))
    )
    (net (code "173") (name "RUN") (class "Default")
      (node (ref "D40") (pin "33") (pinfunction "33_33") (pintype "passive"))
      (node (ref "F40TOP") (pin "18") (pinfunction "1_18") (pintype "passive"))
      (node (ref "T75") (pin "2") (pinfunction "B_2") (pintype "passive"))
    )
    (net (code "174") (name "SC0") (class "Default")
      (node (ref "C40") (pin "9") (pinfunction "9_9") (pintype "passive"))
      (node (ref "C40TOP") (pin "5") (pinfunction "1_5") (pintype "passive"))
      (node (ref "T67") (pin "2") (pinfunction "B_2") (pintype "passive"))
    )
    (net (code "175") (name "SC1") (class "Default")
      (node (ref "C40") (pin "2") (pinfunction "2_2") (pintype "passive"))
      (node (ref "C40BOT") (pin "1") (pinfunction "1_1") (pintype "passive"))
      (node (ref "T68") (pin "2") (pinfunction "B_2") (pintype "passive"))
    )
    (net (code "176") (name "SC2") (class "Default")
      (node (ref "C40") (pin "23") (pinfunction "23_23") (pintype "passive"))
      (node (ref "C40TOP") (pin "13") (pinfunction "1_13") (pintype "passive"))
      (node (ref "T69") (pin "2") (pinfunction "B_2") (pintype "passive"))
    )
    (net (code "177") (name "SC3") (class "Default")
      (node (ref "C40") (pin "12") (pinfunction "12_12") (pintype "passive"))
      (node (ref "C40BOT") (pin "6") (pinfunction "1_6") (pintype "passive"))
      (node (ref "T70") (pin "2") (pinfunction "B_2") (pintype "passive"))
    )
    (net (code "178") (name "SC4") (class "Default")
      (node (ref "C40") (pin "33") (pinfunction "33_33") (pintype "passive"))
      (node (ref "C40TOP") (pin "18") (pinfunction "1_18") (pintype "passive"))
      (node (ref "T71") (pin "2") (pinfunction "B_2") (pintype "passive"))
    )
    (net (code "179") (name "TAD") (class "Default")
      (node (ref "D40") (pin "4") (pinfunction "4_4") (pintype "passive"))
      (node (ref "F40BOT") (pin "2") (pinfunction "1_2") (pintype "passive"))
      (node (ref "T83") (pin "2") (pinfunction "B_2") (pintype "passive"))
    )
    (net (code "180") (name "WC") (class "Default")
      (node (ref "D40") (pin "30") (pinfunction "30_30") (pintype "passive"))
      (node (ref "F40BOT") (pin "17") (pinfunction "1_17") (pintype "passive"))
      (node (ref "T79") (pin "2") (pinfunction "B_2") (pintype "passive"))
    )
    (net (code "181") (name "unconnected-(C40-Pad3)") (class "Default")
      (node (ref "C40") (pin "3") (pinfunction "3_3") (pintype "passive"))
    )
    (net (code "182") (name "unconnected-(C40-Pad4)") (class "Default")
      (node (ref "C40") (pin "4") (pinfunction "4_4") (pintype "passive"))
    )
    (net (code "183") (name "unconnected-(C40-Pad5)") (class "Default")
      (node (ref "C40") (pin "5") (pinfunction "5_5") (pintype "passive"))
    )
    (net (code "184") (name "unconnected-(C40-Pad6)") (class "Default")
      (node (ref "C40") (pin "6") (pinfunction "6_6") (pintype "passive"))
    )
    (net (code "185") (name "unconnected-(C40-Pad7)") (class "Default")
      (node (ref "C40") (pin "7") (pinfunction "7_7") (pintype "passive"))
    )
    (net (code "186") (name "unconnected-(C40-Pad8)") (class "Default")
      (node (ref "C40") (pin "8") (pinfunction "8_8") (pintype "passive"))
    )
    (net (code "187") (name "unconnected-(C40-Pad13)") (class "Default")
      (node (ref "C40") (pin "13") (pinfunction "13_13") (pintype "passive"))
    )
    (net (code "188") (name "unconnected-(C40-Pad14)") (class "Default")
      (node (ref "C40") (pin "14") (pinfunction "14_14") (pintype "passive"))
    )
    (net (code "189") (name "unconnected-(C40-Pad15)") (class "Default")
      (node (ref "C40") (pin "15") (pinfunction "15_15") (pintype "passive"))
    )
    (net (code "190") (name "unconnected-(C40-Pad16)") (class "Default")
      (node (ref "C40") (pin "16") (pinfunction "16_16") (pintype "passive"))
    )
    (net (code "191") (name "unconnected-(C40-Pad21)") (class "Default")
      (node (ref "C40") (pin "21") (pinfunction "21_21") (pintype "passive"))
    )
    (net (code "192") (name "unconnected-(C40-Pad22)") (class "Default")
      (node (ref "C40") (pin "22") (pinfunction "22_22") (pintype "passive"))
    )
    (net (code "193") (name "unconnected-(C40-Pad26)") (class "Default")
      (node (ref "C40") (pin "26") (pinfunction "26_26") (pintype "passive"))
    )
    (net (code "194") (name "unconnected-(C40-Pad27)") (class "Default")
      (node (ref "C40") (pin "27") (pinfunction "27_27") (pintype "passive"))
    )
    (net (code "195") (name "unconnected-(C40-Pad29)") (class "Default")
      (node (ref "C40") (pin "29") (pinfunction "29_29") (pintype "passive"))
    )
    (net (code "196") (name "unconnected-(C40-Pad30)") (class "Default")
      (node (ref "C40") (pin "30") (pinfunction "30_30") (pintype "passive"))
    )
    (net (code "197") (name "unconnected-(C40-Pad31)") (class "Default")
      (node (ref "C40") (pin "31") (pinfunction "31_31") (pintype "passive"))
    )
    (net (code "198") (name "unconnected-(C40-Pad32)") (class "Default")
      (node (ref "C40") (pin "32") (pinfunction "32_32") (pintype "passive"))
    )
    (net (code "199") (name "unconnected-(D40-Pad1)") (class "Default")
      (node (ref "D40") (pin "1") (pinfunction "1_1") (pintype "passive"))
    )
    (net (code "200") (name "unconnected-(D40-Pad3)") (class "Default")
      (node (ref "D40") (pin "3") (pinfunction "3_3") (pintype "passive"))
    )
    (net (code "201") (name "unconnected-(D40-Pad5)") (class "Default")
      (node (ref "D40") (pin "5") (pinfunction "5_5") (pintype "passive"))
    )
    (net (code "202") (name "unconnected-(D40-Pad7)") (class "Default")
      (node (ref "D40") (pin "7") (pinfunction "7_7") (pintype "passive"))
    )
    (net (code "203") (name "unconnected-(D40-Pad9)") (class "Default")
      (node (ref "D40") (pin "9") (pinfunction "9_9") (pintype "passive"))
    )
    (net (code "204") (name "unconnected-(D40-Pad11)") (class "Default")
      (node (ref "D40") (pin "11") (pinfunction "11_11") (pintype "passive"))
    )
    (net (code "205") (name "unconnected-(D40-Pad13)") (class "Default")
      (node (ref "D40") (pin "13") (pinfunction "13_13") (pintype "passive"))
    )
    (net (code "206") (name "unconnected-(D40-Pad14)") (class "Default")
      (node (ref "D40") (pin "14") (pinfunction "14_14") (pintype "passive"))
    )
    (net (code "207") (name "unconnected-(D40-Pad15)") (class "Default")
      (node (ref "D40") (pin "15") (pinfunction "15_15") (pintype "passive"))
    )
    (net (code "208") (name "unconnected-(D40-Pad21)") (class "Default")
      (node (ref "D40") (pin "21") (pinfunction "21_21") (pintype "passive"))
    )
    (net (code "209") (name "unconnected-(D40-Pad25)") (class "Default")
      (node (ref "D40") (pin "25") (pinfunction "25_25") (pintype "passive"))
    )
    (net (code "210") (name "unconnected-(D40-Pad27)") (class "Default")
      (node (ref "D40") (pin "27") (pinfunction "27_27") (pintype "passive"))
    )
    (net (code "211") (name "unconnected-(D40-Pad29)") (class "Default")
      (node (ref "D40") (pin "29") (pinfunction "29_29") (pintype "passive"))
    )
  )
)
